# N-CW7_Main.net
KiCad netlist of a schematic drawn in Altium Designer
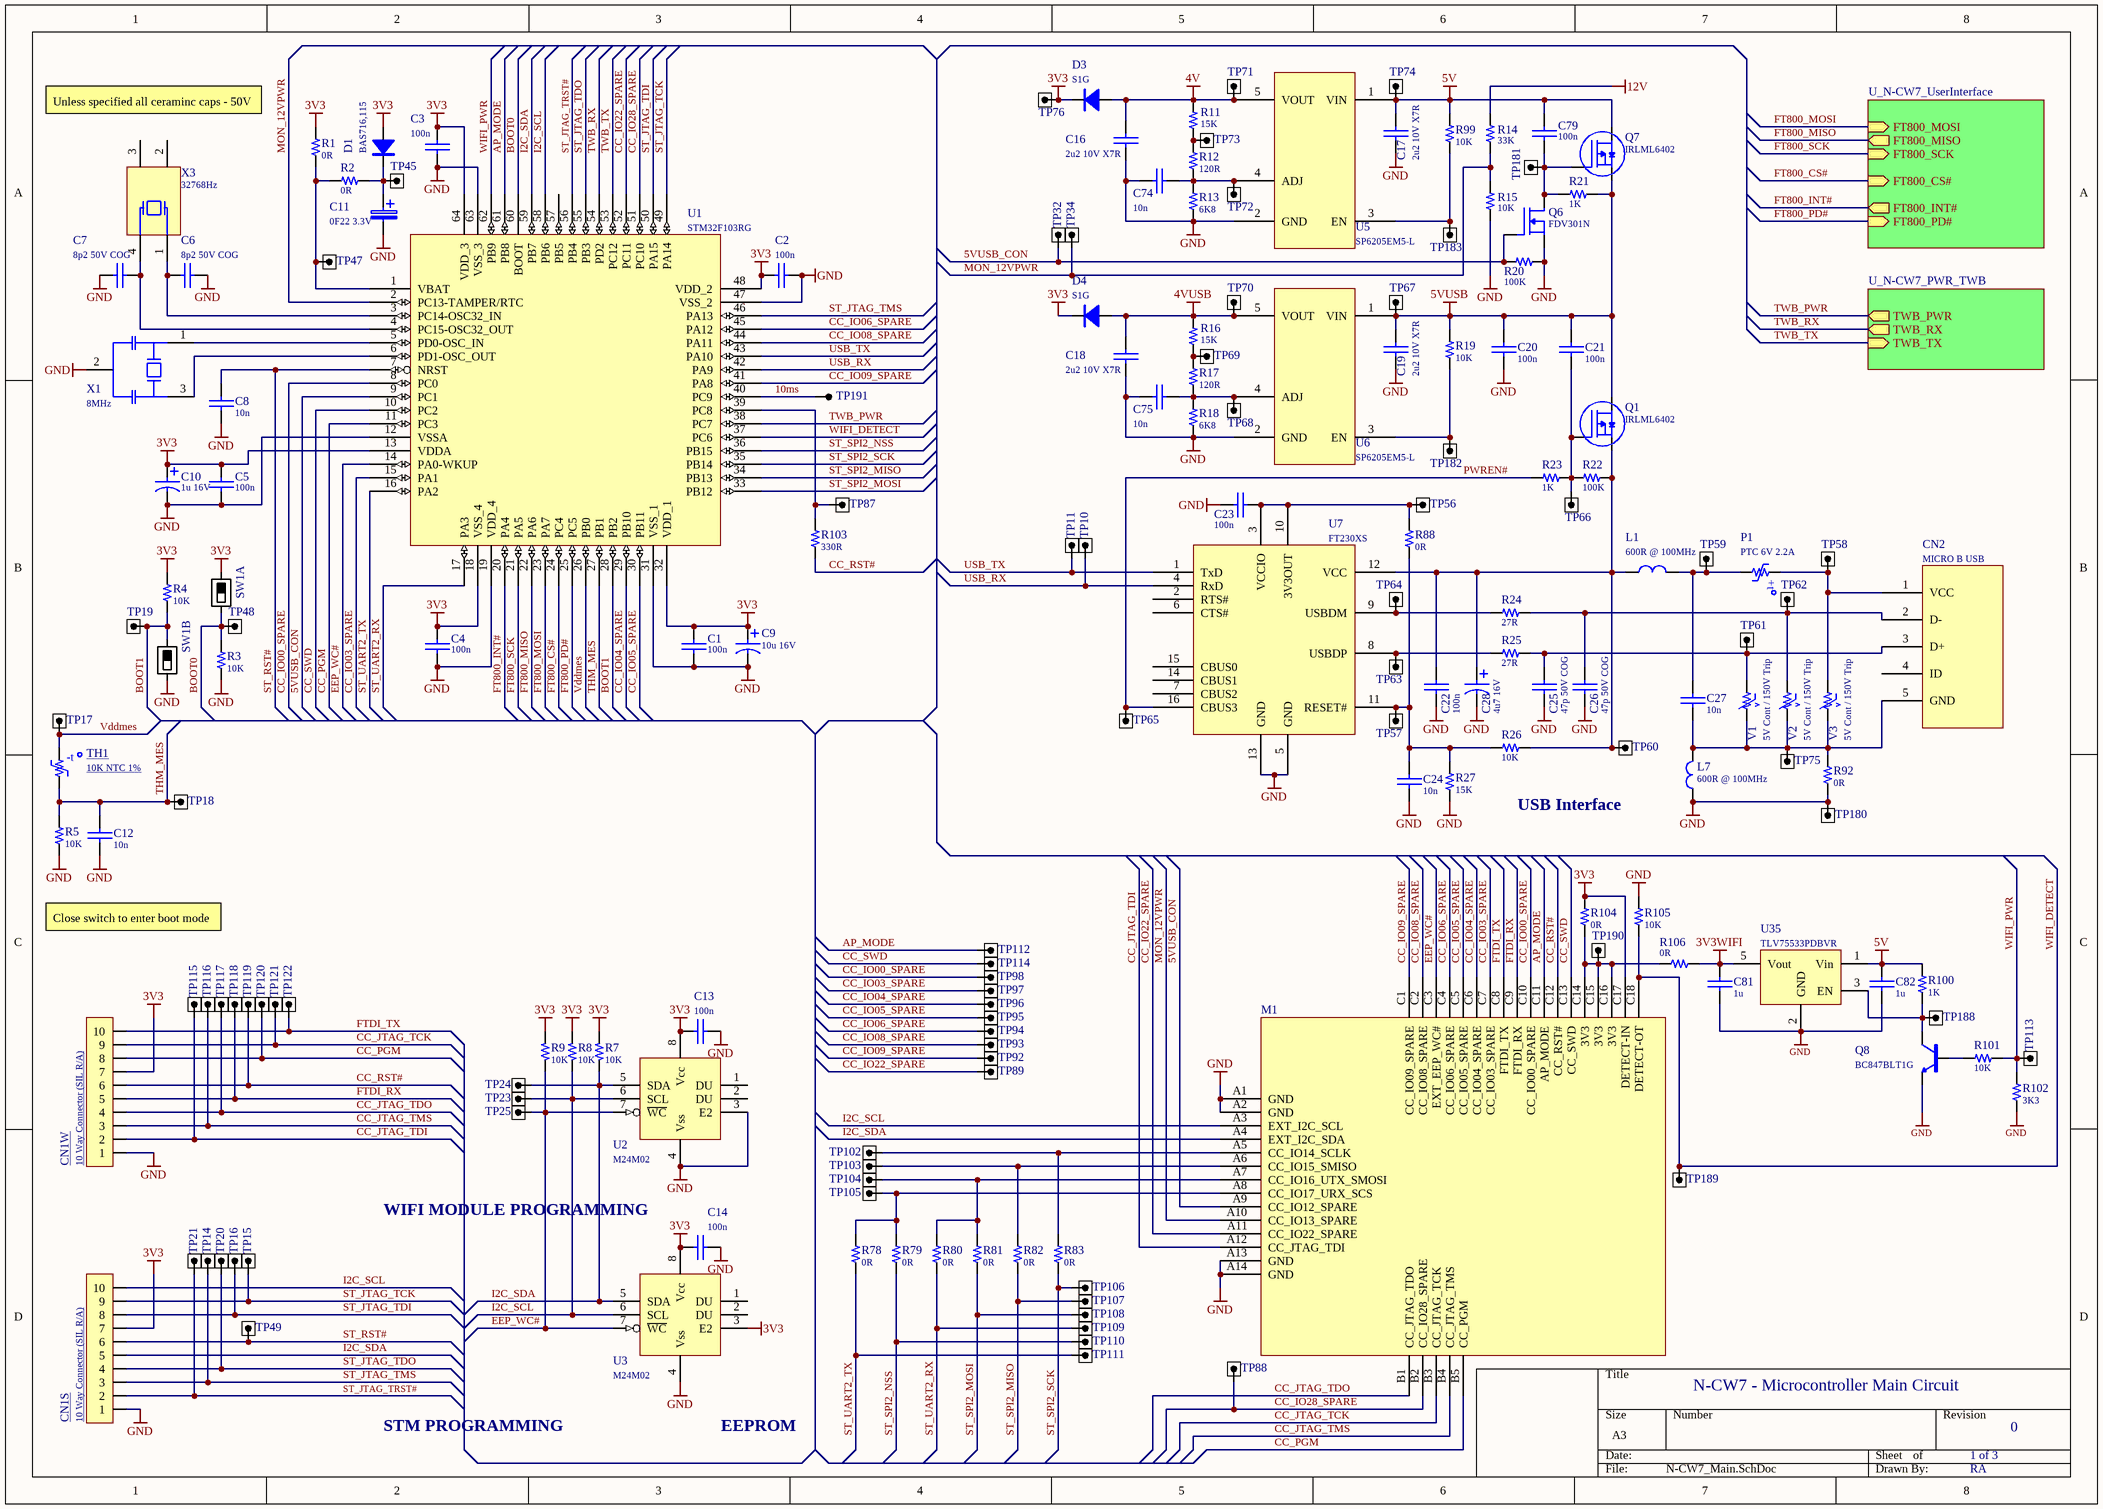
[diagram p0: N-CW7_Main.SchDoc]

(export (version "E")
  (design (tool "Eeschema 10.0.6"))
  (components
    (comp (ref "C1")
      (value "100n")
      (footprint "TDK_0603_T0.80:CAPC1608X08N")
      (description "CAP CER 0.1UF 50V X7R 0603")
      (fields
        (field (name "MANUFACTURER") "TDK")
        (field (name "MANUFACTURER PART NUMBER") "C1608X7R1H104K080AA")
      )
      (libsource (lib "PassiveComponents_Capacitors_Ceramic") (part "TDK_0603_T0.80"))
    )
    (comp (ref "C2")
      (value "100n")
      (footprint "TDK_0603_T0.80:CAPC1608X08N")
      (description "CAP CER 0.1UF 50V X7R 0603")
      (fields
        (field (name "MANUFACTURER") "TDK")
        (field (name "MANUFACTURER PART NUMBER") "C1608X7R1H104K080AA")
      )
      (libsource (lib "PassiveComponents_Capacitors_Ceramic") (part "TDK_0603_T0.80"))
    )
    (comp (ref "C3")
      (value "100n")
      (footprint "TDK_0603_T0.80:CAPC1608X08N")
      (description "CAP CER 0.1UF 50V X7R 0603")
      (fields
        (field (name "MANUFACTURER") "TDK")
        (field (name "MANUFACTURER PART NUMBER") "C1608X7R1H104K080AA")
      )
      (libsource (lib "PassiveComponents_Capacitors_Ceramic") (part "TDK_0603_T0.80"))
    )
    (comp (ref "C4")
      (value "100n")
      (footprint "TDK_0603_T0.80:CAPC1608X08N")
      (description "CAP CER 0.1UF 50V X7R 0603")
      (fields
        (field (name "MANUFACTURER") "TDK")
        (field (name "MANUFACTURER PART NUMBER") "C1608X7R1H104K080AA")
      )
      (libsource (lib "PassiveComponents_Capacitors_Ceramic") (part "TDK_0603_T0.80"))
    )
    (comp (ref "C5")
      (value "100n")
      (footprint "TDK_0603_T0.80:CAPC1608X08N")
      (description "CAP CER 0.1UF 50V X7R 0603")
      (fields
        (field (name "MANUFACTURER") "TDK")
        (field (name "MANUFACTURER PART NUMBER") "C1608X7R1H104K080AA")
      )
      (libsource (lib "PassiveComponents_Capacitors_Ceramic") (part "TDK_0603_T0.80"))
    )
    (comp (ref "C6")
      (value "8p2 50V COG")
      (footprint "KEMET_0603_T0.80:CAPC1608X08N")
      (description "CAP CER 8.2PF 50V C0G/NP0 0603")
      (fields
        (field (name "MANUFACTURER") "KEMET")
        (field (name "MANUFACTURER PART NUMBER") "C0603C829C5GACTU")
      )
      (libsource (lib "PassiveComponents_Capacitors_Ceramic") (part "KEMET_0603_T0.80"))
    )
    (comp (ref "C7")
      (value "8p2 50V COG")
      (footprint "KEMET_0603_T0.80:CAPC1608X08N")
      (description "CAP CER 8.2PF 50V C0G/NP0 0603")
      (fields
        (field (name "MANUFACTURER") "KEMET")
        (field (name "MANUFACTURER PART NUMBER") "C0603C829C5GACTU")
      )
      (libsource (lib "PassiveComponents_Capacitors_Ceramic") (part "KEMET_0603_T0.80"))
    )
    (comp (ref "C8")
      (value "10n")
      (footprint "TDK_0603_T0.80:CAPC1608X08N")
      (description "CAP CER 10000PF 50V X7R 0603")
      (fields
        (field (name "MANUFACTURER") "TDK")
        (field (name "MANUFACTURER PART NUMBER") "C1608X7R1H103K080AA")
      )
      (libsource (lib "PassiveComponents_Capacitors_Ceramic") (part "TDK_0603_T0.80"))
    )
    (comp (ref "C9")
      (value "10u 16V")
      (footprint "KEMET_T494B/3528-21:CAPMP3528X19N")
      (description "CAP TANT 10UF 10% 16V 1411")
      (fields
        (field (name "MANUFACTURER") "KEMET")
        (field (name "MANUFACTURER PART NUMBER") "T494B106K016AT")
      )
      (libsource (lib "PassiveComponents_Capacitors_Tantalum") (part "KEMET_T494B/EIA3528-21"))
    )
    (comp (ref "C10")
      (value "1u 16V")
      (footprint "KEMET_T494A/3216-18:CAPCP3216X16N")
      (description "CAP TANT 1UF 10% 16V 1206")
      (fields
        (field (name "MANUFACTURER") "KEMET")
        (field (name "MANUFACTURER PART NUMBER") "T494A105K016AT")
      )
      (libsource (lib "PassiveComponents_Capacitors_Tantalum") (part "KEMET_T494A/EIA3216-18"))
    )
    (comp (ref "C11")
      (value "0F22 3.3V")
      (footprint "ELNA_RSCSK2243R3D02008U")
      (description "CAP 220MF -20% +80% 3.3V SMD")
      (fields
        (field (name "MANUFACTURER") "Elna")
        (field (name "MANUFACTURER PART NUMBER") "RSCSK2243R3D02008U")
      )
      (libsource (lib "PassiveComponents_Capacitors_Electrolytic") (part "ELNA_RSCSK2243R3D02008U"))
    )
    (comp (ref "C12")
      (value "10n")
      (footprint "TDK_0603_T0.80:CAPC1608X08N")
      (description "CAP CER 10000PF 50V X7R 0603")
      (fields
        (field (name "MANUFACTURER") "TDK")
        (field (name "MANUFACTURER PART NUMBER") "C1608X7R1H103K080AA")
      )
      (libsource (lib "PassiveComponents_Capacitors_Ceramic") (part "TDK_0603_T0.80"))
    )
    (comp (ref "C13")
      (value "100n")
      (footprint "TDK_0603_T0.80:CAPC1608X08N")
      (description "CAP CER 0.1UF 50V X7R 0603")
      (fields
        (field (name "MANUFACTURER") "TDK")
        (field (name "MANUFACTURER PART NUMBER") "C1608X7R1H104K080AA")
      )
      (libsource (lib "PassiveComponents_Capacitors_Ceramic") (part "TDK_0603_T0.80"))
    )
    (comp (ref "C14")
      (value "100n")
      (footprint "TDK_0603_T0.80:CAPC1608X08N")
      (description "CAP CER 0.1UF 50V X7R 0603")
      (fields
        (field (name "MANUFACTURER") "TDK")
        (field (name "MANUFACTURER PART NUMBER") "C1608X7R1H104K080AA")
      )
      (libsource (lib "PassiveComponents_Capacitors_Ceramic") (part "TDK_0603_T0.80"))
    )
    (comp (ref "C16")
      (value "2u2 10V X7R")
      (footprint "TDK_0603_T0.80:CAPC1608X08N")
      (description "CAP CER 2.2UF 10V X7R 0603")
      (fields
        (field (name "MANUFACTURER") "TDK")
        (field (name "MANUFACTURER PART NUMBER") "C1608X7R1A225K080AC")
      )
      (libsource (lib "PassiveComponents_Capacitors_Ceramic") (part "TDK_0603_T0.80"))
    )
    (comp (ref "C17")
      (value "2u2 10V X7R")
      (footprint "TDK_0603_T0.80:CAPC1608X08N")
      (description "CAP CER 2.2UF 10V X7R 0603")
      (fields
        (field (name "MANUFACTURER") "TDK")
        (field (name "MANUFACTURER PART NUMBER") "C1608X7R1A225K080AC")
      )
      (libsource (lib "PassiveComponents_Capacitors_Ceramic") (part "TDK_0603_T0.80"))
    )
    (comp (ref "C18")
      (value "2u2 10V X7R")
      (footprint "TDK_0603_T0.80:CAPC1608X08N")
      (description "CAP CER 2.2UF 10V X7R 0603")
      (fields
        (field (name "MANUFACTURER") "TDK")
        (field (name "MANUFACTURER PART NUMBER") "C1608X7R1A225K080AC")
      )
      (libsource (lib "PassiveComponents_Capacitors_Ceramic") (part "TDK_0603_T0.80"))
    )
    (comp (ref "C19")
      (value "2u2 10V X7R")
      (footprint "TDK_0603_T0.80:CAPC1608X08N")
      (description "CAP CER 2.2UF 10V X7R 0603")
      (fields
        (field (name "MANUFACTURER") "TDK")
        (field (name "MANUFACTURER PART NUMBER") "C1608X7R1A225K080AC")
      )
      (libsource (lib "PassiveComponents_Capacitors_Ceramic") (part "TDK_0603_T0.80"))
    )
    (comp (ref "C20")
      (value "100n")
      (footprint "TDK_0603_T0.80:CAPC1608X08N")
      (description "CAP CER 0.1UF 50V X7R 0603")
      (fields
        (field (name "MANUFACTURER") "TDK")
        (field (name "MANUFACTURER PART NUMBER") "C1608X7R1H104K080AA")
      )
      (libsource (lib "PassiveComponents_Capacitors_Ceramic") (part "TDK_0603_T0.80"))
    )
    (comp (ref "C21")
      (value "100n")
      (footprint "TDK_0603_T0.80:CAPC1608X08N")
      (description "CAP CER 0.1UF 50V X7R 0603")
      (fields
        (field (name "MANUFACTURER") "TDK")
        (field (name "MANUFACTURER PART NUMBER") "C1608X7R1H104K080AA")
      )
      (libsource (lib "PassiveComponents_Capacitors_Ceramic") (part "TDK_0603_T0.80"))
    )
    (comp (ref "C22")
      (value "100n")
      (footprint "TDK_0603_T0.80:CAPC1608X08N")
      (description "CAP CER 0.1UF 50V X7R 0603")
      (fields
        (field (name "MANUFACTURER") "TDK")
        (field (name "MANUFACTURER PART NUMBER") "C1608X7R1H104K080AA")
      )
      (libsource (lib "PassiveComponents_Capacitors_Ceramic") (part "TDK_0603_T0.80"))
    )
    (comp (ref "C23")
      (value "100n")
      (footprint "TDK_0603_T0.80:CAPC1608X08N")
      (description "CAP CER 0.1UF 50V X7R 0603")
      (fields
        (field (name "MANUFACTURER") "TDK")
        (field (name "MANUFACTURER PART NUMBER") "C1608X7R1H104K080AA")
      )
      (libsource (lib "PassiveComponents_Capacitors_Ceramic") (part "TDK_0603_T0.80"))
    )
    (comp (ref "C24")
      (value "10n")
      (footprint "TDK_0603_T0.80:CAPC1608X08N")
      (description "CAP CER 10000PF 50V X7R 0603")
      (fields
        (field (name "MANUFACTURER") "TDK")
        (field (name "MANUFACTURER PART NUMBER") "C1608X7R1H103K080AA")
      )
      (libsource (lib "PassiveComponents_Capacitors_Ceramic") (part "TDK_0603_T0.80"))
    )
    (comp (ref "C25")
      (value "47p 50V COG")
      (footprint "TDK_0603_T0.80:CAPC1608X08N")
      (description "CAP CER 47PF 50V C0G 0603")
      (fields
        (field (name "MANUFACTURER") "TDK")
        (field (name "MANUFACTURER PART NUMBER") "C1608C0G1H470J080AA")
      )
      (libsource (lib "PassiveComponents_Capacitors_Ceramic") (part "TDK_0603_T0.80"))
    )
    (comp (ref "C26")
      (value "47p 50V COG")
      (footprint "TDK_0603_T0.80:CAPC1608X08N")
      (description "CAP CER 47PF 50V C0G 0603")
      (fields
        (field (name "MANUFACTURER") "TDK")
        (field (name "MANUFACTURER PART NUMBER") "C1608C0G1H470J080AA")
      )
      (libsource (lib "PassiveComponents_Capacitors_Ceramic") (part "TDK_0603_T0.80"))
    )
    (comp (ref "C27")
      (value "10n")
      (footprint "TDK_0603_T0.80:CAPC1608X08N")
      (description "CAP CER 10000PF 50V X7R 0603")
      (fields
        (field (name "MANUFACTURER") "TDK")
        (field (name "MANUFACTURER PART NUMBER") "C1608X7R1H103K080AA")
      )
      (libsource (lib "PassiveComponents_Capacitors_Ceramic") (part "TDK_0603_T0.80"))
    )
    (comp (ref "C28")
      (value "4u7 16V")
      (footprint "KEMET_T494A/3216-18:CAPCP3216X16N")
      (description "CAP TANT 4.7UF 10% 16V 1206")
      (fields
        (field (name "MANUFACTURER") "KEMET")
        (field (name "MANUFACTURER PART NUMBER") "T494A475K016AT")
      )
      (libsource (lib "PassiveComponents_Capacitors_Tantalum") (part "KEMET_T494A/EIA3216-18"))
    )
    (comp (ref "C74")
      (value "10n")
      (footprint "TDK_0603_T0.80:CAPC1608X08N")
      (description "CAP CER 10000PF 50V X7R 0603")
      (fields
        (field (name "MANUFACTURER") "TDK")
        (field (name "MANUFACTURER PART NUMBER") "C1608X7R1H103K080AA")
      )
      (libsource (lib "PassiveComponents_Capacitors_Ceramic") (part "TDK_0603_T0.80"))
    )
    (comp (ref "C75")
      (value "10n")
      (footprint "TDK_0603_T0.80:CAPC1608X08N")
      (description "CAP CER 10000PF 50V X7R 0603")
      (fields
        (field (name "MANUFACTURER") "TDK")
        (field (name "MANUFACTURER PART NUMBER") "C1608X7R1H103K080AA")
      )
      (libsource (lib "PassiveComponents_Capacitors_Ceramic") (part "TDK_0603_T0.80"))
    )
    (comp (ref "C79")
      (value "100n")
      (footprint "TDK_0603_T0.80:CAPC1608X08N")
      (description "CAP CER 0.1UF 50V X7R 0603")
      (fields
        (field (name "MANUFACTURER") "TDK")
        (field (name "MANUFACTURER PART NUMBER") "C1608X7R1H104K080AA")
      )
      (libsource (lib "PassiveComponents_Capacitors_Ceramic") (part "TDK_0603_T0.80"))
    )
    (comp (ref "C81")
      (value "1u")
      (footprint "KEMET_1210_T1.55:CAPC3225X16N")
      (description "CAP CER 1UF 50V X5R 1210")
      (fields
        (field (name "MANUFACTURER") "KEMET")
        (field (name "MANUFACTURER PART NUMBER") "C1210C105K5PACTU")
      )
      (libsource (lib "PassiveComponents_Capacitors_Ceramic") (part "KEMET_1210_T1.55"))
    )
    (comp (ref "C82")
      (value "1u")
      (footprint "KEMET_1210_T1.55:CAPC3225X16N")
      (description "CAP CER 1UF 50V X5R 1210")
      (fields
        (field (name "MANUFACTURER") "KEMET")
        (field (name "MANUFACTURER PART NUMBER") "C1210C105K5PACTU")
      )
      (libsource (lib "PassiveComponents_Capacitors_Ceramic") (part "KEMET_1210_T1.55"))
    )
    (comp (ref "CN1S")
      (value "10 Way Connector (SIL R/A)")
      (footprint "SULLINS_PPTC101LGBN-RC")
      (description "CONN HDR 10POS 0.1 TIN PCB R/A")
      (fields
        (field (name "MANUFACTURER") "Sullins")
        (field (name "MANUFACTURER PART NUMBER") "PPTC101LGBN-RC")
      )
      (libsource (lib "Connectors") (part "SULLINS_10W_SIL_HDR_RA_2.54MM"))
    )
    (comp (ref "CN1W")
      (value "10 Way Connector (SIL R/A)")
      (footprint "SULLINS_PPTC101LGBN-RC")
      (description "CONN HDR 10POS 0.1 TIN PCB R/A")
      (fields
        (field (name "MANUFACTURER") "Sullins")
        (field (name "MANUFACTURER PART NUMBER") "PPTC101LGBN-RC")
      )
      (libsource (lib "Connectors") (part "SULLINS_10W_SIL_HDR_RA_2.54MM"))
    )
    (comp (ref "CN2")
      (value "MICRO B USB")
      (footprint "MOLEX:47346-1001")
      (description "CONN RCPT USB2.0 MICRO B SMD R/A")
      (fields (field (name "MANUFACTURER") "Molex") (field (name "MANUFACTURER PART NUMBER") "47346-1001"))
      (libsource (lib "Connectors") (part "MOLEX_USB_MICRO_B_SMD_RA"))
    )
    (comp (ref "D1")
      (value "BAS716,115")
      (footprint "NEXPERIA_BAS716,115_SOD523:SODFL160X65-2N")
      (description "DIODE STANDARD 75V 200MA SOD523")
      (fields (field (name "MANUFACTURER") "Nexperia") (field (name "MANUFACTURER PART NUMBER") "BAS716115"))
      (libsource (lib "DiscreteSemiconductors_Diodes_Rectifier") (part "NEXPERIA_BAS716,115_SOD523"))
    )
    (comp (ref "D3")
      (value "S1G")
      (footprint "DIODESINC_S1G_SMA_D0214AC:DIOM4326X24N")
      (description "DIODE GEN PURP 400V 1A SMA")
      (fields (field (name "MANUFACTURER") "Diodes") (field (name "MANUFACTURER PART NUMBER") "S1G-13-F"))
      (libsource (lib "DiscreteSemiconductors_Diodes_Rectifier") (part "DIODESINC_S1G_SMA_D0214AC"))
    )
    (comp (ref "D4")
      (value "S1G")
      (footprint "DIODESINC_S1G_SMA_D0214AC:DIOM4326X24N")
      (description "DIODE GEN PURP 400V 1A SMA")
      (fields (field (name "MANUFACTURER") "Diodes") (field (name "MANUFACTURER PART NUMBER") "S1G-13-F"))
      (libsource (lib "DiscreteSemiconductors_Diodes_Rectifier") (part "DIODESINC_S1G_SMA_D0214AC"))
    )
    (comp (ref "L1")
      (value "600R @ 100MHz")
      (footprint "LAIRD_MI0805K601R-10:INDC2012X09N")
      (description "FERRITE BEAD 600 OHM 0805 1LN")
      (fields
        (field (name "MANUFACTURER") "Laird")
        (field (name "MANUFACTURER PART NUMBER") "MI0805K601R-10")
      )
      (libsource (lib "PassiveComponents_Inductors") (part "LAIRD_MI0805K601R-10"))
    )
    (comp (ref "L7")
      (value "600R @ 100MHz")
      (footprint "LAIRD_MI0805K601R-10:INDC2012X09N")
      (description "FERRITE BEAD 600 OHM 0805 1LN")
      (fields
        (field (name "MANUFACTURER") "Laird")
        (field (name "MANUFACTURER PART NUMBER") "MI0805K601R-10")
      )
      (libsource (lib "PassiveComponents_Inductors") (part "LAIRD_MI0805K601R-10"))
    )
    (comp (ref "M1")
      (value "MB-WIFI-CC3200Rev00")
      (footprint "MB-WIFI-CC3200Rev00")
      (description "Module - Wi-Fi Module (CC3200)")
      (libsource (lib "CustomModules") (part "MB-WIFI-CC3200Rev00"))
    )
    (comp (ref "P1")
      (value "PTC 6V 2.2A")
      (footprint "BOURNS_MF-MSMF110-2:INDC4632X08N")
      (description "PTC RESET FUSE 24V 1.1A 1812")
      (fields
        (field (name "MANUFACTURER") "Bourns")
        (field (name "MANUFACTURER PART NUMBER") "MF-MSMF110/24X-2")
      )
      (libsource (lib "CircuitProtection_Fuses") (part "BOURNS_MF-MSMF110-2"))
    )
    (comp (ref "Q1")
      (value "IRLML6402")
      (footprint "IR_IRLML6402TRPBF_SOT23:SOT95P237X112-3N")
      (description "MOSFET P-CH 20V 3.7A SOT23")
      (fields
        (field (name "MANUFACTURER") "Infineon")
        (field (name "MANUFACTURER PART NUMBER") "IRLML6402TRPBF")
      )
      (libsource (lib "DiscreteSemiconductors_Transistors_JFETs") (part "IR_IRLML6402TRPBF_SOT23"))
    )
    (comp (ref "Q6")
      (value "FDV301N")
      (footprint "ONSEMI_FDV301N_SOT23:SOT95P230X110-3N")
      (description "MOSFET N-CH 25V 220MA SOT23")
      (fields (field (name "MANUFACTURER") "ON Semiconductor / Fairchild"))
      (libsource (lib "DiscreteSemiconductors_Transistors_JFETs") (part "ONSEMI_FDV301N_SOT23"))
    )
    (comp (ref "Q7")
      (value "IRLML6402")
      (footprint "IR_IRLML6402TRPBF_SOT23:SOT95P237X112-3N")
      (description "MOSFET P-CH 20V 3.7A SOT23")
      (fields
        (field (name "MANUFACTURER") "Infineon")
        (field (name "MANUFACTURER PART NUMBER") "IRLML6402TRPBF")
      )
      (libsource (lib "DiscreteSemiconductors_Transistors_JFETs") (part "IR_IRLML6402TRPBF_SOT23"))
    )
    (comp (ref "Q8")
      (value "BC847BLT1G")
      (footprint "ONSEMI_BC847BLT1G_SOT23:SOT95P230X110-3N")
      (description "TRANS NPN 45V 100MA SOT23-3")
      (fields (field (name "MANUFACTURER") "ON Semiconductor"))
      (libsource (lib "DiscreteSemiconductors_Transistors_BJTs") (part "ONSEMI_BC847BLT1G_SOT23"))
    )
    (comp (ref "R1")
      (value "0R")
      (footprint "YAGEO_0603_T0.55:RESC1608X06N")
      (description "RES 0 OHM JUMPER 1/10W 0603")
      (fields
        (field (name "MANUFACTURER") "Yageo")
        (field (name "MANUFACTURER PART NUMBER") "RC0603FR-070RL")
      )
      (libsource (lib "PassiveComponents_Resistors_ChipSMD") (part "YAGEO_0603_T0.55"))
    )
    (comp (ref "R2")
      (value "0R")
      (footprint "YAGEO_0603_T0.55:RESC1608X06N")
      (description "RES 0 OHM JUMPER 1/10W 0603")
      (fields
        (field (name "MANUFACTURER") "Yageo")
        (field (name "MANUFACTURER PART NUMBER") "RC0603FR-070RL")
      )
      (libsource (lib "PassiveComponents_Resistors_ChipSMD") (part "YAGEO_0603_T0.55"))
    )
    (comp (ref "R3")
      (value "10K")
      (footprint "YAGEO_0603_T0.55:RESC1608X06N")
      (description "RES 10K OHM 1% 1/10W 0603")
      (fields
        (field (name "MANUFACTURER") "Yageo")
        (field (name "MANUFACTURER PART NUMBER") "RC0603FR-0710KL")
      )
      (libsource (lib "PassiveComponents_Resistors_ChipSMD") (part "YAGEO_0603_T0.55"))
    )
    (comp (ref "R4")
      (value "10K")
      (footprint "YAGEO_0603_T0.55:RESC1608X06N")
      (description "RES 10K OHM 1% 1/10W 0603")
      (fields
        (field (name "MANUFACTURER") "Yageo")
        (field (name "MANUFACTURER PART NUMBER") "RC0603FR-0710KL")
      )
      (libsource (lib "PassiveComponents_Resistors_ChipSMD") (part "YAGEO_0603_T0.55"))
    )
    (comp (ref "R5")
      (value "10K")
      (footprint "YAGEO_0603_T0.55:RESC1608X06N")
      (description "RES 10K OHM 1% 1/10W 0603")
      (fields
        (field (name "MANUFACTURER") "Yageo")
        (field (name "MANUFACTURER PART NUMBER") "RC0603FR-0710KL")
      )
      (libsource (lib "PassiveComponents_Resistors_ChipSMD") (part "YAGEO_0603_T0.55"))
    )
    (comp (ref "R7")
      (value "10K")
      (footprint "YAGEO_0603_T0.55:RESC1608X06N")
      (description "RES 10K OHM 1% 1/10W 0603")
      (fields
        (field (name "MANUFACTURER") "Yageo")
        (field (name "MANUFACTURER PART NUMBER") "RC0603FR-0710KL")
      )
      (libsource (lib "PassiveComponents_Resistors_ChipSMD") (part "YAGEO_0603_T0.55"))
    )
    (comp (ref "R8")
      (value "10K")
      (footprint "YAGEO_0603_T0.55:RESC1608X06N")
      (description "RES 10K OHM 1% 1/10W 0603")
      (fields
        (field (name "MANUFACTURER") "Yageo")
        (field (name "MANUFACTURER PART NUMBER") "RC0603FR-0710KL")
      )
      (libsource (lib "PassiveComponents_Resistors_ChipSMD") (part "YAGEO_0603_T0.55"))
    )
    (comp (ref "R9")
      (value "10K")
      (footprint "YAGEO_0603_T0.55:RESC1608X06N")
      (description "RES 10K OHM 1% 1/10W 0603")
      (fields
        (field (name "MANUFACTURER") "Yageo")
        (field (name "MANUFACTURER PART NUMBER") "RC0603FR-0710KL")
      )
      (libsource (lib "PassiveComponents_Resistors_ChipSMD") (part "YAGEO_0603_T0.55"))
    )
    (comp (ref "R11")
      (value "15K")
      (footprint "YAGEO_0603_T0.55:RESC1608X06N")
      (description "RES 15K OHM 1% 1/10W 0603")
      (fields
        (field (name "MANUFACTURER") "Yageo")
        (field (name "MANUFACTURER PART NUMBER") "RC0603FR-0715KL")
      )
      (libsource (lib "PassiveComponents_Resistors_ChipSMD") (part "YAGEO_0603_T0.55"))
    )
    (comp (ref "R12")
      (value "120R")
      (footprint "YAGEO_0603_T0.55:RESC1608X06N")
      (description "RES 120 OHM 1% 1/10W 0603")
      (fields
        (field (name "MANUFACTURER") "Yageo")
        (field (name "MANUFACTURER PART NUMBER") "RC0603FR-07120RL")
      )
      (libsource (lib "PassiveComponents_Resistors_ChipSMD") (part "YAGEO_0603_T0.55"))
    )
    (comp (ref "R13")
      (value "6K8")
      (footprint "YAGEO_0603_T0.55:RESC1608X06N")
      (description "RES 6.8K OHM 1% 1/10W 0603")
      (fields
        (field (name "MANUFACTURER") "Yageo")
        (field (name "MANUFACTURER PART NUMBER") "RC0603FR-076K8L")
      )
      (libsource (lib "PassiveComponents_Resistors_ChipSMD") (part "YAGEO_0603_T0.55"))
    )
    (comp (ref "R14")
      (value "33K")
      (footprint "YAGEO_0603_T0.55:RESC1608X06N")
      (description "RES 33K OHM 1% 1/10W 0603")
      (fields
        (field (name "MANUFACTURER") "Yageo")
        (field (name "MANUFACTURER PART NUMBER") "RC0603FR-0733KL")
      )
      (libsource (lib "PassiveComponents_Resistors_ChipSMD") (part "YAGEO_0603_T0.55"))
    )
    (comp (ref "R15")
      (value "10K")
      (footprint "YAGEO_0603_T0.55:RESC1608X06N")
      (description "RES 10K OHM 1% 1/10W 0603")
      (fields
        (field (name "MANUFACTURER") "Yageo")
        (field (name "MANUFACTURER PART NUMBER") "RC0603FR-0710KL")
      )
      (libsource (lib "PassiveComponents_Resistors_ChipSMD") (part "YAGEO_0603_T0.55"))
    )
    (comp (ref "R16")
      (value "15K")
      (footprint "YAGEO_0603_T0.55:RESC1608X06N")
      (description "RES 15K OHM 1% 1/10W 0603")
      (fields
        (field (name "MANUFACTURER") "Yageo")
        (field (name "MANUFACTURER PART NUMBER") "RC0603FR-0715KL")
      )
      (libsource (lib "PassiveComponents_Resistors_ChipSMD") (part "YAGEO_0603_T0.55"))
    )
    (comp (ref "R17")
      (value "120R")
      (footprint "YAGEO_0603_T0.55:RESC1608X06N")
      (description "RES 120 OHM 1% 1/10W 0603")
      (fields
        (field (name "MANUFACTURER") "Yageo")
        (field (name "MANUFACTURER PART NUMBER") "RC0603FR-07120RL")
      )
      (libsource (lib "PassiveComponents_Resistors_ChipSMD") (part "YAGEO_0603_T0.55"))
    )
    (comp (ref "R18")
      (value "6K8")
      (footprint "YAGEO_0603_T0.55:RESC1608X06N")
      (description "RES 6.8K OHM 1% 1/10W 0603")
      (fields
        (field (name "MANUFACTURER") "Yageo")
        (field (name "MANUFACTURER PART NUMBER") "RC0603FR-076K8L")
      )
      (libsource (lib "PassiveComponents_Resistors_ChipSMD") (part "YAGEO_0603_T0.55"))
    )
    (comp (ref "R19")
      (value "10K")
      (footprint "YAGEO_0603_T0.55:RESC1608X06N")
      (description "RES 10K OHM 1% 1/10W 0603")
      (fields
        (field (name "MANUFACTURER") "Yageo")
        (field (name "MANUFACTURER PART NUMBER") "RC0603FR-0710KL")
      )
      (libsource (lib "PassiveComponents_Resistors_ChipSMD") (part "YAGEO_0603_T0.55"))
    )
    (comp (ref "R20")
      (value "100K")
      (footprint "YAGEO_0603_T0.55:RESC1608X06N")
      (description "RES 100K OHM 1% 1/10W 0603")
      (fields
        (field (name "MANUFACTURER") "Yageo")
        (field (name "MANUFACTURER PART NUMBER") "RC0603FR-07100KL")
      )
      (libsource (lib "PassiveComponents_Resistors_ChipSMD") (part "YAGEO_0603_T0.55"))
    )
    (comp (ref "R21")
      (value "1K")
      (footprint "YAGEO_0603_T0.55:RESC1608X06N")
      (description "RES 1K OHM 1% 1/10W 0603")
      (fields
        (field (name "MANUFACTURER") "Yageo")
        (field (name "MANUFACTURER PART NUMBER") "RC0603FR-071KL")
      )
      (libsource (lib "PassiveComponents_Resistors_ChipSMD") (part "YAGEO_0603_T0.55"))
    )
    (comp (ref "R22")
      (value "100K")
      (footprint "YAGEO_0603_T0.55:RESC1608X06N")
      (description "RES 100K OHM 1% 1/10W 0603")
      (fields
        (field (name "MANUFACTURER") "Yageo")
        (field (name "MANUFACTURER PART NUMBER") "RC0603FR-07100KL")
      )
      (libsource (lib "PassiveComponents_Resistors_ChipSMD") (part "YAGEO_0603_T0.55"))
    )
    (comp (ref "R23")
      (value "1K")
      (footprint "YAGEO_0603_T0.55:RESC1608X06N")
      (description "RES 1K OHM 1% 1/10W 0603")
      (fields
        (field (name "MANUFACTURER") "Yageo")
        (field (name "MANUFACTURER PART NUMBER") "RC0603FR-071KL")
      )
      (libsource (lib "PassiveComponents_Resistors_ChipSMD") (part "YAGEO_0603_T0.55"))
    )
    (comp (ref "R24")
      (value "27R")
      (footprint "YAGEO_0603_T0.55:RESC1608X06N")
      (description "RES 27 OHM 1% 1/10W 0603")
      (fields
        (field (name "MANUFACTURER") "Yageo")
        (field (name "MANUFACTURER PART NUMBER") "RC0603FR-0727RL")
      )
      (libsource (lib "PassiveComponents_Resistors_ChipSMD") (part "YAGEO_0603_T0.55"))
    )
    (comp (ref "R25")
      (value "27R")
      (footprint "YAGEO_0603_T0.55:RESC1608X06N")
      (description "RES 27 OHM 1% 1/10W 0603")
      (fields
        (field (name "MANUFACTURER") "Yageo")
        (field (name "MANUFACTURER PART NUMBER") "RC0603FR-0727RL")
      )
      (libsource (lib "PassiveComponents_Resistors_ChipSMD") (part "YAGEO_0603_T0.55"))
    )
    (comp (ref "R26")
      (value "10K")
      (footprint "YAGEO_0603_T0.55:RESC1608X06N")
      (description "RES 10K OHM 1% 1/10W 0603")
      (fields
        (field (name "MANUFACTURER") "Yageo")
        (field (name "MANUFACTURER PART NUMBER") "RC0603FR-0710KL")
      )
      (libsource (lib "PassiveComponents_Resistors_ChipSMD") (part "YAGEO_0603_T0.55"))
    )
    (comp (ref "R27")
      (value "15K")
      (footprint "YAGEO_0603_T0.55:RESC1608X06N")
      (description "RES 15K OHM 1% 1/10W 0603")
      (fields
        (field (name "MANUFACTURER") "Yageo")
        (field (name "MANUFACTURER PART NUMBER") "RC0603FR-0715KL")
      )
      (libsource (lib "PassiveComponents_Resistors_ChipSMD") (part "YAGEO_0603_T0.55"))
    )
    (comp (ref "R78")
      (value "0R")
      (footprint "YAGEO_0603_T0.55:RESC1608X06N")
      (description "RES 0 OHM JUMPER 1/10W 0603")
      (fields
        (field (name "MANUFACTURER") "Yageo")
        (field (name "MANUFACTURER PART NUMBER") "RC0603FR-070RL")
      )
      (libsource (lib "PassiveComponents_Resistors_ChipSMD") (part "YAGEO_0603_T0.55"))
    )
    (comp (ref "R79")
      (value "0R")
      (footprint "YAGEO_0603_T0.55:RESC1608X06N")
      (description "RES 0 OHM JUMPER 1/10W 0603")
      (fields
        (field (name "MANUFACTURER") "Yageo")
        (field (name "MANUFACTURER PART NUMBER") "RC0603FR-070RL")
      )
      (libsource (lib "PassiveComponents_Resistors_ChipSMD") (part "YAGEO_0603_T0.55"))
    )
    (comp (ref "R80")
      (value "0R")
      (footprint "YAGEO_0603_T0.55:RESC1608X06N")
      (description "RES 0 OHM JUMPER 1/10W 0603")
      (fields
        (field (name "MANUFACTURER") "Yageo")
        (field (name "MANUFACTURER PART NUMBER") "RC0603FR-070RL")
      )
      (libsource (lib "PassiveComponents_Resistors_ChipSMD") (part "YAGEO_0603_T0.55"))
    )
    (comp (ref "R81")
      (value "0R")
      (footprint "YAGEO_0603_T0.55:RESC1608X06N")
      (description "RES 0 OHM JUMPER 1/10W 0603")
      (fields
        (field (name "MANUFACTURER") "Yageo")
        (field (name "MANUFACTURER PART NUMBER") "RC0603FR-070RL")
      )
      (libsource (lib "PassiveComponents_Resistors_ChipSMD") (part "YAGEO_0603_T0.55"))
    )
    (comp (ref "R82")
      (value "0R")
      (footprint "YAGEO_0603_T0.55:RESC1608X06N")
      (description "RES 0 OHM JUMPER 1/10W 0603")
      (fields
        (field (name "MANUFACTURER") "Yageo")
        (field (name "MANUFACTURER PART NUMBER") "RC0603FR-070RL")
      )
      (libsource (lib "PassiveComponents_Resistors_ChipSMD") (part "YAGEO_0603_T0.55"))
    )
    (comp (ref "R83")
      (value "0R")
      (footprint "YAGEO_0603_T0.55:RESC1608X06N")
      (description "RES 0 OHM JUMPER 1/10W 0603")
      (fields
        (field (name "MANUFACTURER") "Yageo")
        (field (name "MANUFACTURER PART NUMBER") "RC0603FR-070RL")
      )
      (libsource (lib "PassiveComponents_Resistors_ChipSMD") (part "YAGEO_0603_T0.55"))
    )
    (comp (ref "R88")
      (value "0R")
      (footprint "YAGEO_0603_T0.55:RESC1608X06N")
      (description "RES 0 OHM JUMPER 1/10W 0603")
      (fields
        (field (name "MANUFACTURER") "Yageo")
        (field (name "MANUFACTURER PART NUMBER") "RC0603FR-070RL")
      )
      (libsource (lib "PassiveComponents_Resistors_ChipSMD") (part "YAGEO_0603_T0.55"))
    )
    (comp (ref "R92")
      (value "0R")
      (footprint "YAGEO_0603_T0.55:RESC1608X06N")
      (description "RES 0 OHM JUMPER 1/10W 0603")
      (fields
        (field (name "MANUFACTURER") "Yageo")
        (field (name "MANUFACTURER PART NUMBER") "RC0603FR-070RL")
      )
      (libsource (lib "PassiveComponents_Resistors_ChipSMD") (part "YAGEO_0603_T0.55"))
    )
    (comp (ref "R99")
      (value "10K")
      (footprint "YAGEO_0603_T0.55:RESC1608X06N")
      (description "RES 10K OHM 1% 1/10W 0603")
      (fields
        (field (name "MANUFACTURER") "Yageo")
        (field (name "MANUFACTURER PART NUMBER") "RC0603FR-0710KL")
      )
      (libsource (lib "PassiveComponents_Resistors_ChipSMD") (part "YAGEO_0603_T0.55"))
    )
    (comp (ref "R100")
      (value "1K")
      (footprint "YAGEO_0603_T0.55:RESC1608X06N")
      (description "RES 1K OHM 1% 1/10W 0603")
      (fields
        (field (name "MANUFACTURER") "Yageo")
        (field (name "MANUFACTURER PART NUMBER") "RC0603FR-071KL")
      )
      (libsource (lib "PassiveComponents_Resistors_ChipSMD") (part "YAGEO_0603_T0.55"))
    )
    (comp (ref "R101")
      (value "10K")
      (footprint "YAGEO_0603_T0.55:RESC1608X06N")
      (description "RES 10K OHM 1% 1/10W 0603")
      (fields
        (field (name "MANUFACTURER") "Yageo")
        (field (name "MANUFACTURER PART NUMBER") "RC0603FR-0710KL")
      )
      (libsource (lib "PassiveComponents_Resistors_ChipSMD") (part "YAGEO_0603_T0.55"))
    )
    (comp (ref "R102")
      (value "3K3")
      (footprint "YAGEO_0603_T0.55:RESC1608X06N")
      (description "RES 3.3K OHM 1% 1/10W 0603")
      (fields
        (field (name "MANUFACTURER") "Yageo")
        (field (name "MANUFACTURER PART NUMBER") "RC0603FR-073K3L")
      )
      (libsource (lib "PassiveComponents_Resistors_ChipSMD") (part "YAGEO_0603_T0.55"))
    )
    (comp (ref "R103")
      (value "330R")
      (footprint "YAGEO_0603_T0.55:RESC1608X06N")
      (description "RES 330 OHM 1% 1/10W 0603")
      (fields
        (field (name "MANUFACTURER") "Yageo")
        (field (name "MANUFACTURER PART NUMBER") "RC0603FR-07330RL")
      )
      (libsource (lib "PassiveComponents_Resistors_ChipSMD") (part "YAGEO_0603_T0.55"))
    )
    (comp (ref "R104")
      (value "0R")
      (footprint "YAGEO_0603_T0.55:RESC1608X06N")
      (description "RES 0 OHM JUMPER 1/10W 0603")
      (fields
        (field (name "MANUFACTURER") "Yageo")
        (field (name "MANUFACTURER PART NUMBER") "RC0603FR-070RL")
      )
      (libsource (lib "PassiveComponents_Resistors_ChipSMD") (part "YAGEO_0603_T0.55"))
    )
    (comp (ref "R105")
      (value "10K")
      (footprint "YAGEO_0603_T0.55:RESC1608X06N")
      (description "RES 10K OHM 1% 1/10W 0603")
      (fields
        (field (name "MANUFACTURER") "Yageo")
        (field (name "MANUFACTURER PART NUMBER") "RC0603FR-0710KL")
      )
      (libsource (lib "PassiveComponents_Resistors_ChipSMD") (part "YAGEO_0603_T0.55"))
    )
    (comp (ref "R106")
      (value "0R")
      (footprint "YAGEO_0603_T0.55:RESC1608X06N")
      (description "RES 0 OHM JUMPER 1/10W 0603")
      (fields
        (field (name "MANUFACTURER") "Yageo")
        (field (name "MANUFACTURER PART NUMBER") "RC0603FR-070RL")
      )
      (libsource (lib "PassiveComponents_Resistors_ChipSMD") (part "YAGEO_0603_T0.55"))
    )
    (comp (ref "SW1A")
      (value "SPST")
      (footprint "COPAL_CHS-02B")
      (description "SWITCH SLIDE DIP SPST 0.1A 6V")
      (fields (field (name "MANUFACTURER") "Nidec Copal") (field (name "MANUFACTURER PART NUMBER") "CHS-02B"))
      (libsource (lib "PassiveComponents_Switches") (part "COPAL_CHS-02B"))
    )
    (comp (ref "SW1B")
      (value "SPST")
      (footprint "COPAL_CHS-02B")
      (description "SWITCH SLIDE DIP SPST 0.1A 6V")
      (fields (field (name "MANUFACTURER") "Nidec Copal") (field (name "MANUFACTURER PART NUMBER") "CHS-02B"))
      (libsource (lib "PassiveComponents_Switches") (part "COPAL_CHS-02B"))
    )
    (comp (ref "TH1")
      (value "10K NTC 1%")
      (footprint "NETWORKER_THERMISTOR_2.54MM")
      (description "THER 10K 1% LEAD MMC SC25 (450103-006AQ)")
      (libsource (lib "CustomParts") (part "NETWORKER_THERMISTOR"))
    )
    (comp (ref "TP10")
      (value "TESTPOINT_OCTAGONAL")
      (footprint "TESTPOINT_OCTAGONAL")
      (libsource (lib "Miscellaneous") (part "TESTPOINT_OCTAGONAL"))
    )
    (comp (ref "TP11")
      (value "TESTPOINT_OCTAGONAL")
      (footprint "TESTPOINT_OCTAGONAL")
      (libsource (lib "Miscellaneous") (part "TESTPOINT_OCTAGONAL"))
    )
    (comp (ref "TP14")
      (value "TESTPOINT_OCTAGONAL")
      (footprint "TESTPOINT_OCTAGONAL")
      (libsource (lib "Miscellaneous") (part "TESTPOINT_OCTAGONAL"))
    )
    (comp (ref "TP15")
      (value "TESTPOINT_OCTAGONAL")
      (footprint "TESTPOINT_OCTAGONAL")
      (libsource (lib "Miscellaneous") (part "TESTPOINT_OCTAGONAL"))
    )
    (comp (ref "TP16")
      (value "TESTPOINT_OCTAGONAL")
      (footprint "TESTPOINT_OCTAGONAL")
      (libsource (lib "Miscellaneous") (part "TESTPOINT_OCTAGONAL"))
    )
    (comp (ref "TP17")
      (value "TESTPOINT_OCTAGONAL")
      (footprint "TESTPOINT_OCTAGONAL")
      (libsource (lib "Miscellaneous") (part "TESTPOINT_OCTAGONAL"))
    )
    (comp (ref "TP18")
      (value "TESTPOINT_OCTAGONAL")
      (footprint "TESTPOINT_OCTAGONAL")
      (libsource (lib "") (part "TESTPOINT_OCTAGONAL_3"))
    )
    (comp (ref "TP19")
      (value "TESTPOINT_OCTAGONAL")
      (footprint "TESTPOINT_OCTAGONAL")
      (libsource (lib "") (part "TESTPOINT_OCTAGONAL_2"))
    )
    (comp (ref "TP20")
      (value "TESTPOINT_OCTAGONAL")
      (footprint "TESTPOINT_OCTAGONAL")
      (libsource (lib "Miscellaneous") (part "TESTPOINT_OCTAGONAL"))
    )
    (comp (ref "TP21")
      (value "TESTPOINT_OCTAGONAL")
      (footprint "TESTPOINT_OCTAGONAL")
      (libsource (lib "Miscellaneous") (part "TESTPOINT_OCTAGONAL"))
    )
    (comp (ref "TP23")
      (value "TESTPOINT_OCTAGONAL")
      (footprint "TESTPOINT_OCTAGONAL")
      (libsource (lib "") (part "TESTPOINT_OCTAGONAL_2"))
    )
    (comp (ref "TP24")
      (value "TESTPOINT_OCTAGONAL")
      (footprint "TESTPOINT_OCTAGONAL")
      (libsource (lib "") (part "TESTPOINT_OCTAGONAL_2"))
    )
    (comp (ref "TP25")
      (value "TESTPOINT_OCTAGONAL")
      (footprint "TESTPOINT_OCTAGONAL")
      (libsource (lib "") (part "TESTPOINT_OCTAGONAL_2"))
    )
    (comp (ref "TP32")
      (value "TESTPOINT_OCTAGONAL")
      (footprint "TESTPOINT_OCTAGONAL")
      (libsource (lib "Miscellaneous") (part "TESTPOINT_OCTAGONAL"))
    )
    (comp (ref "TP34")
      (value "TESTPOINT_OCTAGONAL")
      (footprint "TESTPOINT_OCTAGONAL")
      (libsource (lib "Miscellaneous") (part "TESTPOINT_OCTAGONAL"))
    )
    (comp (ref "TP45")
      (value "TESTPOINT_OCTAGONAL")
      (footprint "TESTPOINT_OCTAGONAL")
      (libsource (lib "") (part "TESTPOINT_OCTAGONAL_3"))
    )
    (comp (ref "TP47")
      (value "TESTPOINT_OCTAGONAL")
      (footprint "TESTPOINT_OCTAGONAL")
      (libsource (lib "") (part "TESTPOINT_OCTAGONAL_3"))
    )
    (comp (ref "TP48")
      (value "TESTPOINT_OCTAGONAL")
      (footprint "TESTPOINT_OCTAGONAL")
      (libsource (lib "") (part "TESTPOINT_OCTAGONAL_3"))
    )
    (comp (ref "TP49")
      (value "TESTPOINT_OCTAGONAL")
      (footprint "TESTPOINT_OCTAGONAL")
      (libsource (lib "Miscellaneous") (part "TESTPOINT_OCTAGONAL"))
    )
    (comp (ref "TP56")
      (value "TESTPOINT_OCTAGONAL")
      (footprint "TESTPOINT_OCTAGONAL")
      (libsource (lib "") (part "TESTPOINT_OCTAGONAL_3"))
    )
    (comp (ref "TP57")
      (value "TESTPOINT_OCTAGONAL")
      (footprint "TESTPOINT_OCTAGONAL")
      (libsource (lib "") (part "TESTPOINT_OCTAGONAL_1"))
    )
    (comp (ref "TP58")
      (value "TESTPOINT_OCTAGONAL")
      (footprint "TESTPOINT_OCTAGONAL")
      (libsource (lib "Miscellaneous") (part "TESTPOINT_OCTAGONAL"))
    )
    (comp (ref "TP59")
      (value "TESTPOINT_OCTAGONAL")
      (footprint "TESTPOINT_OCTAGONAL")
      (libsource (lib "Miscellaneous") (part "TESTPOINT_OCTAGONAL"))
    )
    (comp (ref "TP60")
      (value "TESTPOINT_OCTAGONAL")
      (footprint "TESTPOINT_OCTAGONAL")
      (libsource (lib "") (part "TESTPOINT_OCTAGONAL_3"))
    )
    (comp (ref "TP61")
      (value "TESTPOINT_OCTAGONAL")
      (footprint "TESTPOINT_OCTAGONAL")
      (libsource (lib "Miscellaneous") (part "TESTPOINT_OCTAGONAL"))
    )
    (comp (ref "TP62")
      (value "TESTPOINT_OCTAGONAL")
      (footprint "TESTPOINT_OCTAGONAL")
      (libsource (lib "Miscellaneous") (part "TESTPOINT_OCTAGONAL"))
    )
    (comp (ref "TP63")
      (value "TESTPOINT_OCTAGONAL")
      (footprint "TESTPOINT_OCTAGONAL")
      (libsource (lib "") (part "TESTPOINT_OCTAGONAL_1"))
    )
    (comp (ref "TP64")
      (value "TESTPOINT_OCTAGONAL")
      (footprint "TESTPOINT_OCTAGONAL")
      (libsource (lib "Miscellaneous") (part "TESTPOINT_OCTAGONAL"))
    )
    (comp (ref "TP65")
      (value "TESTPOINT_OCTAGONAL")
      (footprint "TESTPOINT_OCTAGONAL")
      (libsource (lib "") (part "TESTPOINT_OCTAGONAL_1"))
    )
    (comp (ref "TP66")
      (value "TESTPOINT_OCTAGONAL")
      (footprint "TESTPOINT_OCTAGONAL")
      (libsource (lib "") (part "TESTPOINT_OCTAGONAL_1"))
    )
    (comp (ref "TP67")
      (value "TESTPOINT_OCTAGONAL")
      (footprint "TESTPOINT_OCTAGONAL")
      (libsource (lib "Miscellaneous") (part "TESTPOINT_OCTAGONAL"))
    )
    (comp (ref "TP68")
      (value "TESTPOINT_OCTAGONAL")
      (footprint "TESTPOINT_OCTAGONAL")
      (libsource (lib "") (part "TESTPOINT_OCTAGONAL_1"))
    )
    (comp (ref "TP69")
      (value "TESTPOINT_OCTAGONAL")
      (footprint "TESTPOINT_OCTAGONAL")
      (libsource (lib "") (part "TESTPOINT_OCTAGONAL_3"))
    )
    (comp (ref "TP70")
      (value "TESTPOINT_OCTAGONAL")
      (footprint "TESTPOINT_OCTAGONAL")
      (libsource (lib "Miscellaneous") (part "TESTPOINT_OCTAGONAL"))
    )
    (comp (ref "TP71")
      (value "TESTPOINT_OCTAGONAL")
      (footprint "TESTPOINT_OCTAGONAL")
      (libsource (lib "Miscellaneous") (part "TESTPOINT_OCTAGONAL"))
    )
    (comp (ref "TP72")
      (value "TESTPOINT_OCTAGONAL")
      (footprint "TESTPOINT_OCTAGONAL")
      (libsource (lib "") (part "TESTPOINT_OCTAGONAL_1"))
    )
    (comp (ref "TP73")
      (value "TESTPOINT_OCTAGONAL")
      (footprint "TESTPOINT_OCTAGONAL")
      (libsource (lib "") (part "TESTPOINT_OCTAGONAL_3"))
    )
    (comp (ref "TP74")
      (value "TESTPOINT_OCTAGONAL")
      (footprint "TESTPOINT_OCTAGONAL")
      (libsource (lib "Miscellaneous") (part "TESTPOINT_OCTAGONAL"))
    )
    (comp (ref "TP75")
      (value "TESTPOINT_OCTAGONAL")
      (footprint "TESTPOINT_OCTAGONAL")
      (libsource (lib "") (part "TESTPOINT_OCTAGONAL_1"))
    )
    (comp (ref "TP76")
      (value "TESTPOINT_OCTAGONAL")
      (footprint "TESTPOINT_OCTAGONAL")
      (libsource (lib "") (part "TESTPOINT_OCTAGONAL_2"))
    )
    (comp (ref "TP87")
      (value "TESTPOINT_OCTAGONAL")
      (footprint "TESTPOINT_OCTAGONAL")
      (libsource (lib "") (part "TESTPOINT_OCTAGONAL_3"))
    )
    (comp (ref "TP88")
      (value "TESTPOINT_OCTAGONAL")
      (footprint "TESTPOINT_OCTAGONAL")
      (libsource (lib "Miscellaneous") (part "TESTPOINT_OCTAGONAL"))
    )
    (comp (ref "TP89")
      (value "TESTPOINT_OCTAGONAL")
      (footprint "TESTPOINT_OCTAGONAL")
      (libsource (lib "") (part "TESTPOINT_OCTAGONAL_3"))
    )
    (comp (ref "TP92")
      (value "TESTPOINT_OCTAGONAL")
      (footprint "TESTPOINT_OCTAGONAL")
      (libsource (lib "") (part "TESTPOINT_OCTAGONAL_3"))
    )
    (comp (ref "TP93")
      (value "TESTPOINT_OCTAGONAL")
      (footprint "TESTPOINT_OCTAGONAL")
      (libsource (lib "") (part "TESTPOINT_OCTAGONAL_3"))
    )
    (comp (ref "TP94")
      (value "TESTPOINT_OCTAGONAL")
      (footprint "TESTPOINT_OCTAGONAL")
      (libsource (lib "") (part "TESTPOINT_OCTAGONAL_3"))
    )
    (comp (ref "TP95")
      (value "TESTPOINT_OCTAGONAL")
      (footprint "TESTPOINT_OCTAGONAL")
      (libsource (lib "") (part "TESTPOINT_OCTAGONAL_3"))
    )
    (comp (ref "TP96")
      (value "TESTPOINT_OCTAGONAL")
      (footprint "TESTPOINT_OCTAGONAL")
      (libsource (lib "") (part "TESTPOINT_OCTAGONAL_3"))
    )
    (comp (ref "TP97")
      (value "TESTPOINT_OCTAGONAL")
      (footprint "TESTPOINT_OCTAGONAL")
      (libsource (lib "") (part "TESTPOINT_OCTAGONAL_3"))
    )
    (comp (ref "TP98")
      (value "TESTPOINT_OCTAGONAL")
      (footprint "TESTPOINT_OCTAGONAL")
      (libsource (lib "") (part "TESTPOINT_OCTAGONAL_3"))
    )
    (comp (ref "TP102")
      (value "TESTPOINT_OCTAGONAL")
      (footprint "TESTPOINT_OCTAGONAL")
      (libsource (lib "") (part "TESTPOINT_OCTAGONAL_2"))
    )
    (comp (ref "TP103")
      (value "TESTPOINT_OCTAGONAL")
      (footprint "TESTPOINT_OCTAGONAL")
      (libsource (lib "") (part "TESTPOINT_OCTAGONAL_2"))
    )
    (comp (ref "TP104")
      (value "TESTPOINT_OCTAGONAL")
      (footprint "TESTPOINT_OCTAGONAL")
      (libsource (lib "") (part "TESTPOINT_OCTAGONAL_2"))
    )
    (comp (ref "TP105")
      (value "TESTPOINT_OCTAGONAL")
      (footprint "TESTPOINT_OCTAGONAL")
      (libsource (lib "") (part "TESTPOINT_OCTAGONAL_2"))
    )
    (comp (ref "TP106")
      (value "TESTPOINT_OCTAGONAL")
      (footprint "TESTPOINT_OCTAGONAL")
      (libsource (lib "") (part "TESTPOINT_OCTAGONAL_3"))
    )
    (comp (ref "TP107")
      (value "TESTPOINT_OCTAGONAL")
      (footprint "TESTPOINT_OCTAGONAL")
      (libsource (lib "") (part "TESTPOINT_OCTAGONAL_3"))
    )
    (comp (ref "TP108")
      (value "TESTPOINT_OCTAGONAL")
      (footprint "TESTPOINT_OCTAGONAL")
      (libsource (lib "") (part "TESTPOINT_OCTAGONAL_3"))
    )
    (comp (ref "TP109")
      (value "TESTPOINT_OCTAGONAL")
      (footprint "TESTPOINT_OCTAGONAL")
      (libsource (lib "") (part "TESTPOINT_OCTAGONAL_3"))
    )
    (comp (ref "TP110")
      (value "TESTPOINT_OCTAGONAL")
      (footprint "TESTPOINT_OCTAGONAL")
      (libsource (lib "") (part "TESTPOINT_OCTAGONAL_3"))
    )
    (comp (ref "TP111")
      (value "TESTPOINT_OCTAGONAL")
      (footprint "TESTPOINT_OCTAGONAL")
      (libsource (lib "") (part "TESTPOINT_OCTAGONAL_3"))
    )
    (comp (ref "TP112")
      (value "TESTPOINT_OCTAGONAL")
      (footprint "TESTPOINT_OCTAGONAL")
      (libsource (lib "") (part "TESTPOINT_OCTAGONAL_3"))
    )
    (comp (ref "TP113")
      (value "TESTPOINT_OCTAGONAL")
      (footprint "TESTPOINT_OCTAGONAL")
      (libsource (lib "") (part "TESTPOINT_OCTAGONAL_3"))
    )
    (comp (ref "TP114")
      (value "TESTPOINT_OCTAGONAL")
      (footprint "TESTPOINT_OCTAGONAL")
      (libsource (lib "") (part "TESTPOINT_OCTAGONAL_3"))
    )
    (comp (ref "TP115")
      (value "TESTPOINT_OCTAGONAL")
      (footprint "TESTPOINT_OCTAGONAL")
      (libsource (lib "Miscellaneous") (part "TESTPOINT_OCTAGONAL"))
    )
    (comp (ref "TP116")
      (value "TESTPOINT_OCTAGONAL")
      (footprint "TESTPOINT_OCTAGONAL")
      (libsource (lib "Miscellaneous") (part "TESTPOINT_OCTAGONAL"))
    )
    (comp (ref "TP117")
      (value "TESTPOINT_OCTAGONAL")
      (footprint "TESTPOINT_OCTAGONAL")
      (libsource (lib "Miscellaneous") (part "TESTPOINT_OCTAGONAL"))
    )
    (comp (ref "TP118")
      (value "TESTPOINT_OCTAGONAL")
      (footprint "TESTPOINT_OCTAGONAL")
      (libsource (lib "Miscellaneous") (part "TESTPOINT_OCTAGONAL"))
    )
    (comp (ref "TP119")
      (value "TESTPOINT_OCTAGONAL")
      (footprint "TESTPOINT_OCTAGONAL")
      (libsource (lib "Miscellaneous") (part "TESTPOINT_OCTAGONAL"))
    )
    (comp (ref "TP120")
      (value "TESTPOINT_OCTAGONAL")
      (footprint "TESTPOINT_OCTAGONAL")
      (libsource (lib "Miscellaneous") (part "TESTPOINT_OCTAGONAL"))
    )
    (comp (ref "TP121")
      (value "TESTPOINT_OCTAGONAL")
      (footprint "TESTPOINT_OCTAGONAL")
      (libsource (lib "Miscellaneous") (part "TESTPOINT_OCTAGONAL"))
    )
    (comp (ref "TP122")
      (value "TESTPOINT_OCTAGONAL")
      (footprint "TESTPOINT_OCTAGONAL")
      (libsource (lib "Miscellaneous") (part "TESTPOINT_OCTAGONAL"))
    )
    (comp (ref "TP180")
      (value "TESTPOINT_OCTAGONAL")
      (footprint "TESTPOINT_OCTAGONAL")
      (libsource (lib "") (part "TESTPOINT_OCTAGONAL_1"))
    )
    (comp (ref "TP181")
      (value "TESTPOINT_OCTAGONAL")
      (footprint "TESTPOINT_OCTAGONAL")
      (libsource (lib "") (part "TESTPOINT_OCTAGONAL_2"))
    )
    (comp (ref "TP182")
      (value "TESTPOINT_OCTAGONAL")
      (footprint "TESTPOINT_OCTAGONAL")
      (libsource (lib "") (part "TESTPOINT_OCTAGONAL_1"))
    )
    (comp (ref "TP183")
      (value "TESTPOINT_OCTAGONAL")
      (footprint "TESTPOINT_OCTAGONAL")
      (libsource (lib "") (part "TESTPOINT_OCTAGONAL_1"))
    )
    (comp (ref "TP188")
      (value "TESTPOINT_OCTAGONAL")
      (footprint "TESTPOINT_OCTAGONAL")
      (libsource (lib "") (part "TESTPOINT_OCTAGONAL_3"))
    )
    (comp (ref "TP189")
      (value "TESTPOINT_OCTAGONAL")
      (footprint "TESTPOINT_OCTAGONAL")
      (libsource (lib "") (part "TESTPOINT_OCTAGONAL_1"))
    )
    (comp (ref "TP190")
      (value "TESTPOINT_OCTAGONAL")
      (footprint "TESTPOINT_OCTAGONAL")
      (libsource (lib "Miscellaneous") (part "TESTPOINT_OCTAGONAL"))
    )
    (comp (ref "TP191")
      (value "TESTPOINT_ROUND")
      (footprint "TESTPOINT_ROUND")
      (libsource (lib "Miscellaneous") (part "TESTPOINT_ROUND"))
    )
    (comp (ref "U1")
      (value "STM32F103RG")
      (footprint "STM_STM32F103RG_LQFP64:TSQFP50P1200X1200X160-64N")
      (description "IC MCU 32BIT 1MB FLASH 64LQFP")
      (fields
        (field (name "MANUFACTURER") "STMicroelectronics")
        (field (name "MANUFACTURER PART NUMBER") "STM32F103RGT6")
      )
      (libsource (lib "IntegratedCircuits_Embedded_Microcontrollers") (part "STM_STM32F103RG_LQFP64"))
    )
    (comp (ref "U2")
      (value "M24M02")
      (footprint "STM_M24M02-DR_SOIC8:SOIC127P600X175-8N")
      (description "IC EEPROM 2MBIT I2C 1MHZ 8SO")
      (fields
        (field (name "MANUFACTURER") "STMicroelectronics")
        (field (name "MANUFACTURER PART NUMBER") "M24M02-DRMN6TP")
      )
      (libsource (lib "IntegratedCircuits_Memory_EEPROM") (part "STM_M24M02-DR_SOIC8"))
    )
    (comp (ref "U3")
      (value "M24M02")
      (footprint "STM_M24M02-DR_SOIC8:SOIC127P600X175-8N")
      (description "IC EEPROM 2MBIT I2C 1MHZ 8SO")
      (fields
        (field (name "MANUFACTURER") "STMicroelectronics")
        (field (name "MANUFACTURER PART NUMBER") "M24M02-DRMN6TP")
      )
      (libsource (lib "IntegratedCircuits_Memory_EEPROM") (part "STM_M24M02-DR_SOIC8"))
    )
    (comp (ref "U5")
      (value "SP6205EM5-L")
      (footprint "EXAR_SP6205EM5-L_SOT23_5:SOT95P280X145-5N")
      (description "IC REG LIN POS ADJ 500MA SOT23-5")
      (fields (field (name "MANUFACTURER") "Exar") (field (name "MANUFACTURER PART NUMBER") "SP6205EM5-L/TR"))
      (libsource (lib "IntegratedCircuits_Power_VoltageRegsLinear") (part "EXAR_SP6205EM5-L_SOT23_5"))
    )
    (comp (ref "U6")
      (value "SP6205EM5-L")
      (footprint "EXAR_SP6205EM5-L_SOT23_5:SOT95P280X145-5N")
      (description "IC REG LIN POS ADJ 500MA SOT23-5")
      (fields (field (name "MANUFACTURER") "Exar") (field (name "MANUFACTURER PART NUMBER") "SP6205EM5-L/TR"))
      (libsource (lib "IntegratedCircuits_Power_VoltageRegsLinear") (part "EXAR_SP6205EM5-L_SOT23_5"))
    )
    (comp (ref "U7")
      (value "FT230XS")
      (footprint "FTDI_FT230XS_SOP64P600X175-16N")
      (description "IC USB SERIAL BASIC UART 16SSOP")
      (fields (field (name "MANUFACTURER") "FTDI") (field (name "MANUFACTURER PART NUMBER") "FT230XS-U"))
      (libsource (lib "IntegratedCircuits_Interface_RSType") (part "FTDI_FT230XS_SSOP16"))
    )
    (comp (ref "U35")
      (value "TLV75533PDBVR")
      (footprint "TI_TLV75533PDBVR_SOT23_5:SOT95P280X145-5N")
      (description "IC REG LINEAR 3.3V 500MA SOT23-5")
      (fields (field (name "MANUFACTURER") "Texas Instruments"))
      (libsource (lib "IntegratedCircuits_Power_VoltageRegsLinear") (part "TI_TLV75533PDBVR_SOT23_5"))
    )
    (comp (ref "V1")
      (value "5V Cont / 150V Trip")
      (footprint "BOURNS_CGA0603MLC:INDC1608X04N")
      (description "VARISTOR 0603")
      (fields
        (field (name "MANUFACTURER") "Bourns")
        (field (name "MANUFACTURER PART NUMBER") "CG0603MLC-05E")
      )
      (libsource (lib "CircuitProtection_Varistors") (part "BOURNS_CGA0603MLC"))
    )
    (comp (ref "V2")
      (value "5V Cont / 150V Trip")
      (footprint "BOURNS_CGA0603MLC:INDC1608X04N")
      (description "VARISTOR 0603")
      (fields
        (field (name "MANUFACTURER") "Bourns")
        (field (name "MANUFACTURER PART NUMBER") "CG0603MLC-05E")
      )
      (libsource (lib "CircuitProtection_Varistors") (part "BOURNS_CGA0603MLC"))
    )
    (comp (ref "V3")
      (value "5V Cont / 150V Trip")
      (footprint "BOURNS_CGA0603MLC:INDC1608X04N")
      (description "VARISTOR 0603")
      (fields
        (field (name "MANUFACTURER") "Bourns")
        (field (name "MANUFACTURER PART NUMBER") "CG0603MLC-05E")
      )
      (libsource (lib "CircuitProtection_Varistors") (part "BOURNS_CGA0603MLC"))
    )
    (comp (ref "X1")
      (value "8MHz")
      (footprint "MURATA_CSTNE8M00G550000R0")
      (description "CERAMIC RES 8.0000MHZ 33PF SMD")
      (fields
        (field (name "MANUFACTURER") "Murata")
        (field (name "MANUFACTURER PART NUMBER") "CSTNE8M00G550000R0")
      )
      (libsource (lib "PassiveComponents_Oscillators_Resonators") (part "MURATA_CSTNE8M00G550000R0"))
    )
    (comp (ref "X3")
      (value "32768Hz")
      (footprint "EPSON_MC-146")
      (description "CRYSTAL 32.7680KHZ 12.5PF SMD")
      (fields
        (field (name "MANUFACTURER") "Epson")
        (field (name "MANUFACTURER PART NUMBER") "MC-14632.7680KA-A0:ROHS")
      )
      (libsource (lib "PassiveComponents_Oscillators_Resonators") (part "EPSON_MC-146"))
    )
  )
  (nets
    (net (code "1") (name "/5VUSB_CON") (class "Default")
      (node (ref "M1") (pin "A9") (pinfunction "CC_IO12_SPARE_A9") (pintype "passive"))
      (node (ref "Q6") (pin "1") (pinfunction "G_1") (pintype "passive"))
      (node (ref "R20") (pin "2") (pinfunction "2_2") (pintype "passive"))
      (node (ref "TP32") (pin "1") (pinfunction "1_1") (pintype "passive"))
      (node (ref "U1") (pin "9") (pinfunction "PC1_9") (pintype "bidirectional"))
    )
    (net (code "2") (name "/10ms") (class "Default")
      (node (ref "TP191") (pin "1") (pinfunction "1_1") (pintype "passive"))
      (node (ref "U1") (pin "40") (pinfunction "PC9_40") (pintype "bidirectional"))
    )
    (net (code "3") (name "/AP_MODE") (class "Default")
      (node (ref "M1") (pin "C11") (pinfunction "AP_MODE_C11") (pintype "passive"))
      (node (ref "TP112") (pin "1") (pinfunction "1_1") (pintype "passive"))
      (node (ref "U1") (pin "61") (pinfunction "PB8_61") (pintype "bidirectional"))
    )
    (net (code "4") (name "/BOOT0") (class "Default")
      (node (ref "R3") (pin "2") (pinfunction "2_2") (pintype "passive"))
      (node (ref "SW1A") (pin "2") (pinfunction "2_2") (pintype "passive"))
      (node (ref "TP48") (pin "1") (pinfunction "1_1") (pintype "passive"))
      (node (ref "U1") (pin "60") (pinfunction "BOOT_60") (pintype "passive"))
    )
    (net (code "5") (name "/BOOT1") (class "Default")
      (node (ref "R4") (pin "1") (pinfunction "1_1") (pintype "passive"))
      (node (ref "SW1B") (pin "1") (pinfunction "1_1") (pintype "passive"))
      (node (ref "TP19") (pin "1") (pinfunction "1_1") (pintype "passive"))
      (node (ref "U1") (pin "28") (pinfunction "PB2_28") (pintype "bidirectional"))
    )
    (net (code "6") (name "/CC_IO00_SPARE") (class "Default")
      (node (ref "M1") (pin "C10") (pinfunction "CC_IO00_SPARE_C10") (pintype "passive"))
      (node (ref "TP98") (pin "1") (pinfunction "1_1") (pintype "passive"))
      (node (ref "U1") (pin "8") (pinfunction "PC0_8") (pintype "bidirectional"))
    )
    (net (code "7") (name "/CC_IO03_SPARE") (class "Default")
      (node (ref "M1") (pin "C7") (pinfunction "CC_IO03_SPARE_C7") (pintype "passive"))
      (node (ref "TP97") (pin "1") (pinfunction "1_1") (pintype "passive"))
      (node (ref "U1") (pin "15") (pinfunction "PA1_15") (pintype "bidirectional"))
    )
    (net (code "8") (name "/CC_IO04_SPARE") (class "Default")
      (node (ref "M1") (pin "C6") (pinfunction "CC_IO04_SPARE_C6") (pintype "passive"))
      (node (ref "TP96") (pin "1") (pinfunction "1_1") (pintype "passive"))
      (node (ref "U1") (pin "29") (pinfunction "PB10_29") (pintype "bidirectional"))
    )
    (net (code "9") (name "/CC_IO05_SPARE") (class "Default")
      (node (ref "M1") (pin "C5") (pinfunction "CC_IO05_SPARE_C5") (pintype "passive"))
      (node (ref "TP95") (pin "1") (pinfunction "1_1") (pintype "passive"))
      (node (ref "U1") (pin "30") (pinfunction "PB11_30") (pintype "bidirectional"))
    )
    (net (code "10") (name "/CC_IO06_SPARE") (class "Default")
      (node (ref "M1") (pin "C4") (pinfunction "CC_IO06_SPARE_C4") (pintype "passive"))
      (node (ref "TP94") (pin "1") (pinfunction "1_1") (pintype "passive"))
      (node (ref "U1") (pin "45") (pinfunction "PA12_45") (pintype "bidirectional"))
    )
    (net (code "11") (name "/CC_IO08_SPARE") (class "Default")
      (node (ref "M1") (pin "C2") (pinfunction "CC_IO08_SPARE_C2") (pintype "passive"))
      (node (ref "TP93") (pin "1") (pinfunction "1_1") (pintype "passive"))
      (node (ref "U1") (pin "44") (pinfunction "PA11_44") (pintype "bidirectional"))
    )
    (net (code "12") (name "/CC_IO09_SPARE") (class "Default")
      (node (ref "M1") (pin "C1") (pinfunction "CC_IO09_SPARE_C1") (pintype "passive"))
      (node (ref "TP92") (pin "1") (pinfunction "1_1") (pintype "passive"))
      (node (ref "U1") (pin "41") (pinfunction "PA8_41") (pintype "bidirectional"))
    )
    (net (code "13") (name "/CC_IO22_SPARE") (class "Default")
      (node (ref "M1") (pin "A11") (pinfunction "CC_IO22_SPARE_A11") (pintype "passive"))
      (node (ref "TP89") (pin "1") (pinfunction "1_1") (pintype "passive"))
      (node (ref "U1") (pin "52") (pinfunction "PC11_52") (pintype "bidirectional"))
    )
    (net (code "14") (name "/CC_IO28_SPARE") (class "Default")
      (node (ref "M1") (pin "B2") (pinfunction "CC_IO28_SPARE_B2") (pintype "passive"))
      (node (ref "TP88") (pin "1") (pinfunction "1_1") (pintype "passive"))
      (node (ref "U1") (pin "51") (pinfunction "PC10_51") (pintype "bidirectional"))
    )
    (net (code "15") (name "/CC_JTAG_TCK") (class "Default")
      (node (ref "CN1W") (pin "9") (pinfunction "9_9") (pintype "passive"))
      (node (ref "M1") (pin "B3") (pinfunction "CC_JTAG_TCK_B3") (pintype "passive"))
      (node (ref "TP121") (pin "1") (pinfunction "1_1") (pintype "passive"))
    )
    (net (code "16") (name "/CC_JTAG_TDI") (class "Default")
      (node (ref "CN1W") (pin "2") (pinfunction "2_2") (pintype "passive"))
      (node (ref "M1") (pin "A12") (pinfunction "CC_JTAG_TDI_A12") (pintype "passive"))
      (node (ref "TP115") (pin "1") (pinfunction "1_1") (pintype "passive"))
    )
    (net (code "17") (name "/CC_JTAG_TDO") (class "Default")
      (node (ref "CN1W") (pin "4") (pinfunction "4_4") (pintype "passive"))
      (node (ref "M1") (pin "B1") (pinfunction "CC_JTAG_TDO_B1") (pintype "passive"))
      (node (ref "TP117") (pin "1") (pinfunction "1_1") (pintype "passive"))
    )
    (net (code "18") (name "/CC_JTAG_TMS") (class "Default")
      (node (ref "CN1W") (pin "3") (pinfunction "3_3") (pintype "passive"))
      (node (ref "M1") (pin "B4") (pinfunction "CC_JTAG_TMS_B4") (pintype "passive"))
      (node (ref "TP116") (pin "1") (pinfunction "1_1") (pintype "passive"))
    )
    (net (code "19") (name "/CC_PGM") (class "Default")
      (node (ref "CN1W") (pin "8") (pinfunction "8_8") (pintype "passive"))
      (node (ref "M1") (pin "B5") (pinfunction "CC_PGM_B5") (pintype "passive"))
      (node (ref "TP120") (pin "1") (pinfunction "1_1") (pintype "passive"))
      (node (ref "U1") (pin "11") (pinfunction "PC3_11") (pintype "bidirectional"))
    )
    (net (code "20") (name "/CC_RST#") (class "Default")
      (node (ref "CN1W") (pin "6") (pinfunction "6_6") (pintype "passive"))
      (node (ref "M1") (pin "C12") (pinfunction "CC_RST#_C12") (pintype "passive"))
      (node (ref "R103") (pin "1") (pinfunction "1_1") (pintype "passive"))
      (node (ref "TP119") (pin "1") (pinfunction "1_1") (pintype "passive"))
    )
    (net (code "21") (name "/CC_SWD") (class "Default")
      (node (ref "M1") (pin "C13") (pinfunction "CC_SWD_C13") (pintype "passive"))
      (node (ref "TP114") (pin "1") (pinfunction "1_1") (pintype "passive"))
      (node (ref "U1") (pin "10") (pinfunction "PC2_10") (pintype "bidirectional"))
    )
    (net (code "22") (name "/EEP_WC#") (class "Default")
      (node (ref "M1") (pin "C3") (pinfunction "EXT_EEP_WC#_C3") (pintype "passive"))
      (node (ref "R9") (pin "1") (pinfunction "1_1") (pintype "passive"))
      (node (ref "TP25") (pin "1") (pinfunction "1_1") (pintype "passive"))
      (node (ref "U1") (pin "14") (pinfunction "PA0-WKUP_14") (pintype "bidirectional"))
      (node (ref "U2") (pin "7") (pinfunction "~{WC}_7") (pintype "input"))
      (node (ref "U3") (pin "7") (pinfunction "~{WC}_7") (pintype "input"))
    )
    (net (code "23") (name "/FT800_CS#") (class "Default")
      (node (ref "U1") (pin "24") (pinfunction "PC4_24") (pintype "bidirectional"))
    )
    (net (code "24") (name "/FT800_INT#") (class "Default")
      (node (ref "U1") (pin "20") (pinfunction "PA4_20") (pintype "bidirectional"))
    )
    (net (code "25") (name "/FT800_MISO") (class "Default")
      (node (ref "U1") (pin "22") (pinfunction "PA6_22") (pintype "bidirectional"))
    )
    (net (code "26") (name "/FT800_MOSI") (class "Default")
      (node (ref "U1") (pin "23") (pinfunction "PA7_23") (pintype "bidirectional"))
    )
    (net (code "27") (name "/FT800_PD#") (class "Default")
      (node (ref "U1") (pin "25") (pinfunction "PC5_25") (pintype "bidirectional"))
    )
    (net (code "28") (name "/FT800_SCK") (class "Default")
      (node (ref "U1") (pin "21") (pinfunction "PA5_21") (pintype "bidirectional"))
    )
    (net (code "29") (name "/FTDI_RX") (class "Default")
      (node (ref "CN1W") (pin "5") (pinfunction "5_5") (pintype "passive"))
      (node (ref "M1") (pin "C9") (pinfunction "FTDI_RX_C9") (pintype "passive"))
      (node (ref "TP118") (pin "1") (pinfunction "1_1") (pintype "passive"))
    )
    (net (code "30") (name "/FTDI_TX") (class "Default")
      (node (ref "CN1W") (pin "10") (pinfunction "10_10") (pintype "passive"))
      (node (ref "M1") (pin "C8") (pinfunction "FTDI_TX_C8") (pintype "passive"))
      (node (ref "TP122") (pin "1") (pinfunction "1_1") (pintype "passive"))
    )
    (net (code "31") (name "/I2C_SCL") (class "Default")
      (node (ref "CN1S") (pin "10") (pinfunction "10_10") (pintype "passive"))
      (node (ref "M1") (pin "A3") (pinfunction "EXT_I2C_SCL_A3") (pintype "passive"))
      (node (ref "R8") (pin "1") (pinfunction "1_1") (pintype "passive"))
      (node (ref "TP23") (pin "1") (pinfunction "1_1") (pintype "passive"))
      (node (ref "U1") (pin "58") (pinfunction "PB6_58") (pintype "bidirectional"))
      (node (ref "U2") (pin "6") (pinfunction "SCL_6") (pintype "open_collector"))
      (node (ref "U3") (pin "6") (pinfunction "SCL_6") (pintype "open_collector"))
    )
    (net (code "32") (name "/I2C_SDA") (class "Default")
      (node (ref "CN1S") (pin "5") (pinfunction "5_5") (pintype "passive"))
      (node (ref "M1") (pin "A4") (pinfunction "EXT_I2C_SDA_A4") (pintype "passive"))
      (node (ref "R7") (pin "1") (pinfunction "1_1") (pintype "passive"))
      (node (ref "TP24") (pin "1") (pinfunction "1_1") (pintype "passive"))
      (node (ref "U1") (pin "59") (pinfunction "PB7_59") (pintype "bidirectional"))
      (node (ref "U2") (pin "5") (pinfunction "SDA_5") (pintype "open_collector"))
      (node (ref "U3") (pin "5") (pinfunction "SDA_5") (pintype "open_collector"))
    )
    (net (code "33") (name "/MON_12VPWR") (class "Default")
      (node (ref "M1") (pin "A10") (pinfunction "CC_IO13_SPARE_A10") (pintype "passive"))
      (node (ref "R14") (pin "1") (pinfunction "1_1") (pintype "passive"))
      (node (ref "R15") (pin "2") (pinfunction "2_2") (pintype "passive"))
      (node (ref "TP34") (pin "1") (pinfunction "1_1") (pintype "passive"))
      (node (ref "U1") (pin "2") (pinfunction "PC13-TAMPER/RTC_2") (pintype "bidirectional"))
    )
    (net (code "34") (name "/PWREN#") (class "Default")
      (node (ref "R23") (pin "1") (pinfunction "1_1") (pintype "passive"))
      (node (ref "TP65") (pin "1") (pinfunction "1_1") (pintype "passive"))
      (node (ref "U7") (pin "16") (pinfunction "CBUS3_16") (pintype "passive"))
    )
    (net (code "35") (name "/ST_JTAG_TCK") (class "Default")
      (node (ref "CN1S") (pin "9") (pinfunction "9_9") (pintype "passive"))
      (node (ref "TP15") (pin "1") (pinfunction "1_1") (pintype "passive"))
      (node (ref "U1") (pin "49") (pinfunction "PA14_49") (pintype "bidirectional"))
    )
    (net (code "36") (name "/ST_JTAG_TDI") (class "Default")
      (node (ref "CN1S") (pin "8") (pinfunction "8_8") (pintype "passive"))
      (node (ref "TP16") (pin "1") (pinfunction "1_1") (pintype "passive"))
      (node (ref "U1") (pin "50") (pinfunction "PA15_50") (pintype "bidirectional"))
    )
    (net (code "37") (name "/ST_JTAG_TDO") (class "Default")
      (node (ref "CN1S") (pin "4") (pinfunction "4_4") (pintype "passive"))
      (node (ref "TP20") (pin "1") (pinfunction "1_1") (pintype "passive"))
      (node (ref "U1") (pin "55") (pinfunction "PB3_55") (pintype "bidirectional"))
    )
    (net (code "38") (name "/ST_JTAG_TMS") (class "Default")
      (node (ref "CN1S") (pin "3") (pinfunction "3_3") (pintype "passive"))
      (node (ref "TP14") (pin "1") (pinfunction "1_1") (pintype "passive"))
      (node (ref "U1") (pin "46") (pinfunction "PA13_46") (pintype "bidirectional"))
    )
    (net (code "39") (name "/ST_JTAG_TRST#") (class "Default")
      (node (ref "CN1S") (pin "2") (pinfunction "2_2") (pintype "passive"))
      (node (ref "TP21") (pin "1") (pinfunction "1_1") (pintype "passive"))
      (node (ref "U1") (pin "56") (pinfunction "PB4_56") (pintype "bidirectional"))
    )
    (net (code "40") (name "/ST_RST#") (class "Default")
      (node (ref "C8") (pin "2") (pinfunction "2_2") (pintype "passive"))
      (node (ref "CN1S") (pin "6") (pinfunction "6_6") (pintype "passive"))
      (node (ref "TP49") (pin "1") (pinfunction "1_1") (pintype "passive"))
      (node (ref "U1") (pin "7") (pinfunction "NRST_7") (pintype "bidirectional"))
    )
    (net (code "41") (name "/ST_SPI2_MISO") (class "Default")
      (node (ref "R82") (pin "2") (pinfunction "2_2") (pintype "passive"))
      (node (ref "TP107") (pin "1") (pinfunction "1_1") (pintype "passive"))
      (node (ref "U1") (pin "34") (pinfunction "PB13_34") (pintype "bidirectional"))
    )
    (net (code "42") (name "/ST_SPI2_MOSI") (class "Default")
      (node (ref "R81") (pin "2") (pinfunction "2_2") (pintype "passive"))
      (node (ref "TP108") (pin "1") (pinfunction "1_1") (pintype "passive"))
      (node (ref "U1") (pin "33") (pinfunction "PB12_33") (pintype "bidirectional"))
    )
    (net (code "43") (name "/ST_SPI2_NSS") (class "Default")
      (node (ref "R79") (pin "2") (pinfunction "2_2") (pintype "passive"))
      (node (ref "TP110") (pin "1") (pinfunction "1_1") (pintype "passive"))
      (node (ref "U1") (pin "36") (pinfunction "PB15_36") (pintype "bidirectional"))
    )
    (net (code "44") (name "/ST_SPI2_SCK") (class "Default")
      (node (ref "R83") (pin "2") (pinfunction "2_2") (pintype "passive"))
      (node (ref "TP106") (pin "1") (pinfunction "1_1") (pintype "passive"))
      (node (ref "U1") (pin "35") (pinfunction "PB14_35") (pintype "bidirectional"))
    )
    (net (code "45") (name "/ST_UART2_RX") (class "Default")
      (node (ref "R80") (pin "2") (pinfunction "2_2") (pintype "passive"))
      (node (ref "TP109") (pin "1") (pinfunction "1_1") (pintype "passive"))
      (node (ref "U1") (pin "17") (pinfunction "PA3_17") (pintype "bidirectional"))
    )
    (net (code "46") (name "/ST_UART2_TX") (class "Default")
      (node (ref "R78") (pin "2") (pinfunction "2_2") (pintype "passive"))
      (node (ref "TP111") (pin "1") (pinfunction "1_1") (pintype "passive"))
      (node (ref "U1") (pin "16") (pinfunction "PA2_16") (pintype "bidirectional"))
    )
    (net (code "47") (name "/THM_MES") (class "Default")
      (node (ref "C12") (pin "2") (pinfunction "2_2") (pintype "passive"))
      (node (ref "R5") (pin "2") (pinfunction "2_2") (pintype "passive"))
      (node (ref "TH1") (pin "1") (pinfunction "1_1") (pintype "passive"))
      (node (ref "TP18") (pin "1") (pinfunction "1_1") (pintype "passive"))
      (node (ref "U1") (pin "27") (pinfunction "PB1_27") (pintype "bidirectional"))
    )
    (net (code "48") (name "/TWB_PWR") (class "Default")
      (node (ref "U1") (pin "38") (pinfunction "PC7_38") (pintype "bidirectional"))
    )
    (net (code "49") (name "/TWB_RX") (class "Default")
      (node (ref "U1") (pin "54") (pinfunction "PD2_54") (pintype "bidirectional"))
    )
    (net (code "50") (name "/TWB_TX") (class "Default")
      (node (ref "U1") (pin "53") (pinfunction "PC12_53") (pintype "bidirectional"))
    )
    (net (code "51") (name "/USB_RX") (class "Default")
      (node (ref "TP10") (pin "1") (pinfunction "1_1") (pintype "passive"))
      (node (ref "U1") (pin "42") (pinfunction "PA9_42") (pintype "bidirectional"))
      (node (ref "U7") (pin "4") (pinfunction "RxD_4") (pintype "passive"))
    )
    (net (code "52") (name "/USB_TX") (class "Default")
      (node (ref "TP11") (pin "1") (pinfunction "1_1") (pintype "passive"))
      (node (ref "U1") (pin "43") (pinfunction "PA10_43") (pintype "bidirectional"))
      (node (ref "U7") (pin "1") (pinfunction "TxD_1") (pintype "passive"))
    )
    (net (code "53") (name "/Vddmes") (class "Default")
      (node (ref "TH1") (pin "2") (pinfunction "2_2") (pintype "passive"))
      (node (ref "TP17") (pin "1") (pinfunction "1_1") (pintype "passive"))
      (node (ref "U1") (pin "26") (pinfunction "PB0_26") (pintype "bidirectional"))
    )
    (net (code "54") (name "/WIFI_DETECT") (class "Default")
      (node (ref "M1") (pin "C18") (pinfunction "DETECT-OT_C18") (pintype "passive"))
      (node (ref "R105") (pin "2") (pinfunction "2_2") (pintype "passive"))
      (node (ref "TP189") (pin "1") (pinfunction "1_1") (pintype "passive"))
      (node (ref "U1") (pin "37") (pinfunction "PC6_37") (pintype "bidirectional"))
    )
    (net (code "55") (name "/WIFI_PWR") (class "Default")
      (node (ref "R101") (pin "1") (pinfunction "1_1") (pintype "passive"))
      (node (ref "R102") (pin "1") (pinfunction "1_1") (pintype "passive"))
      (node (ref "TP113") (pin "1") (pinfunction "1_1") (pintype "passive"))
      (node (ref "U1") (pin "62") (pinfunction "PB9_62") (pintype "bidirectional"))
    )
    (net (code "56") (name "3V3") (class "Default")
      (node (ref "C1") (pin "1") (pinfunction "1_1") (pintype "passive"))
      (node (ref "C10") (pin "1") (pinfunction "1_1") (pintype "passive"))
      (node (ref "C13") (pin "2") (pinfunction "2_2") (pintype "passive"))
      (node (ref "C14") (pin "2") (pinfunction "2_2") (pintype "passive"))
      (node (ref "C2") (pin "1") (pinfunction "1_1") (pintype "passive"))
      (node (ref "C3") (pin "1") (pinfunction "1_1") (pintype "passive"))
      (node (ref "C4") (pin "1") (pinfunction "1_1") (pintype "passive"))
      (node (ref "C5") (pin "1") (pinfunction "1_1") (pintype "passive"))
      (node (ref "C9") (pin "1") (pinfunction "1_1") (pintype "passive"))
      (node (ref "CN1S") (pin "7") (pinfunction "7_7") (pintype "passive"))
      (node (ref "CN1W") (pin "7") (pinfunction "7_7") (pintype "passive"))
      (node (ref "D1") (pin "2") (pinfunction "A_2") (pintype "passive"))
      (node (ref "D3") (pin "1") (pinfunction "K_1") (pintype "passive"))
      (node (ref "D4") (pin "1") (pinfunction "K_1") (pintype "passive"))
      (node (ref "M1") (pin "C17") (pinfunction "DETECT-IN_C17") (pintype "passive"))
      (node (ref "R1") (pin "1") (pinfunction "1_1") (pintype "passive"))
      (node (ref "R104") (pin "1") (pinfunction "1_1") (pintype "passive"))
      (node (ref "R4") (pin "2") (pinfunction "2_2") (pintype "passive"))
      (node (ref "R7") (pin "2") (pinfunction "2_2") (pintype "passive"))
      (node (ref "R8") (pin "2") (pinfunction "2_2") (pintype "passive"))
      (node (ref "R9") (pin "2") (pinfunction "2_2") (pintype "passive"))
      (node (ref "SW1A") (pin "1") (pinfunction "1_1") (pintype "passive"))
      (node (ref "TP76") (pin "1") (pinfunction "1_1") (pintype "passive"))
      (node (ref "U1") (pin "13") (pinfunction "VDDA_13") (pintype "power_in"))
      (node (ref "U1") (pin "18") (pinfunction "VSS_4_18") (pintype "power_in"))
      (node (ref "U1") (pin "32") (pinfunction "VDD_1_32") (pintype "power_in"))
      (node (ref "U1") (pin "48") (pinfunction "VDD_2_48") (pintype "power_in"))
      (node (ref "U1") (pin "64") (pinfunction "VDD_3_64") (pintype "power_in"))
      (node (ref "U2") (pin "8") (pinfunction "Vcc_8") (pintype "power_in"))
      (node (ref "U3") (pin "3") (pinfunction "E2_3") (pintype "passive"))
      (node (ref "U3") (pin "8") (pinfunction "Vcc_8") (pintype "power_in"))
    )
    (net (code "57") (name "3V3WIFI") (class "Default")
      (node (ref "C81") (pin "2") (pinfunction "2_2") (pintype "passive"))
      (node (ref "R106") (pin "2") (pinfunction "2_2") (pintype "passive"))
      (node (ref "U35") (pin "5") (pinfunction "Vout_5") (pintype "passive"))
    )
    (net (code "58") (name "4V") (class "Default")
      (node (ref "C16") (pin "2") (pinfunction "2_2") (pintype "passive"))
      (node (ref "D3") (pin "2") (pinfunction "A_2") (pintype "passive"))
      (node (ref "R11") (pin "2") (pinfunction "2_2") (pintype "passive"))
      (node (ref "TP71") (pin "1") (pinfunction "1_1") (pintype "passive"))
      (node (ref "U5") (pin "5") (pinfunction "VOUT_5") (pintype "passive"))
    )
    (net (code "59") (name "4VUSB") (class "Default")
      (node (ref "C18") (pin "2") (pinfunction "2_2") (pintype "passive"))
      (node (ref "D4") (pin "2") (pinfunction "A_2") (pintype "passive"))
      (node (ref "R16") (pin "2") (pinfunction "2_2") (pintype "passive"))
      (node (ref "TP70") (pin "1") (pinfunction "1_1") (pintype "passive"))
      (node (ref "U6") (pin "5") (pinfunction "VOUT_5") (pintype "passive"))
    )
    (net (code "60") (name "5V") (class "Default")
      (node (ref "C17") (pin "2") (pinfunction "2_2") (pintype "passive"))
      (node (ref "C79") (pin "1") (pinfunction "1_1") (pintype "passive"))
      (node (ref "C82") (pin "2") (pinfunction "2_2") (pintype "passive"))
      (node (ref "Q7") (pin "3") (pinfunction "D_3") (pintype "passive"))
      (node (ref "R100") (pin "2") (pinfunction "2_2") (pintype "passive"))
      (node (ref "R99") (pin "1") (pinfunction "1_1") (pintype "passive"))
      (node (ref "TP74") (pin "1") (pinfunction "1_1") (pintype "passive"))
      (node (ref "U35") (pin "1") (pinfunction "Vin_1") (pintype "passive"))
      (node (ref "U5") (pin "1") (pinfunction "VIN_1") (pintype "passive"))
    )
    (net (code "61") (name "5VUSB") (class "Default")
      (node (ref "C19") (pin "2") (pinfunction "2_2") (pintype "passive"))
      (node (ref "C20") (pin "1") (pinfunction "1_1") (pintype "passive"))
      (node (ref "C21") (pin "2") (pinfunction "2_2") (pintype "passive"))
      (node (ref "Q1") (pin "3") (pinfunction "D_3") (pintype "passive"))
      (node (ref "Q7") (pin "2") (pinfunction "S_2") (pintype "passive"))
      (node (ref "R19") (pin "1") (pinfunction "1_1") (pintype "passive"))
      (node (ref "R21") (pin "1") (pinfunction "1_1") (pintype "passive"))
      (node (ref "TP67") (pin "1") (pinfunction "1_1") (pintype "passive"))
      (node (ref "U6") (pin "1") (pinfunction "VIN_1") (pintype "passive"))
    )
    (net (code "62") (name "12V") (class "Default")
      (node (ref "R14") (pin "2") (pinfunction "2_2") (pintype "passive"))
    )
    (net (code "63") (name "GND") (class "Default")
      (node (ref "C1") (pin "2") (pinfunction "2_2") (pintype "passive"))
      (node (ref "C10") (pin "2") (pinfunction "2_2") (pintype "passive"))
      (node (ref "C11") (pin "2") (pinfunction "2_2") (pintype "passive"))
      (node (ref "C12") (pin "1") (pinfunction "1_1") (pintype "passive"))
      (node (ref "C13") (pin "1") (pinfunction "1_1") (pintype "passive"))
      (node (ref "C14") (pin "1") (pinfunction "1_1") (pintype "passive"))
      (node (ref "C16") (pin "1") (pinfunction "1_1") (pintype "passive"))
      (node (ref "C17") (pin "1") (pinfunction "1_1") (pintype "passive"))
      (node (ref "C18") (pin "1") (pinfunction "1_1") (pintype "passive"))
      (node (ref "C19") (pin "1") (pinfunction "1_1") (pintype "passive"))
      (node (ref "C2") (pin "2") (pinfunction "2_2") (pintype "passive"))
      (node (ref "C20") (pin "2") (pinfunction "2_2") (pintype "passive"))
      (node (ref "C22") (pin "2") (pinfunction "2_2") (pintype "passive"))
      (node (ref "C23") (pin "1") (pinfunction "1_1") (pintype "passive"))
      (node (ref "C24") (pin "2") (pinfunction "2_2") (pintype "passive"))
      (node (ref "C25") (pin "1") (pinfunction "1_1") (pintype "passive"))
      (node (ref "C26") (pin "1") (pinfunction "1_1") (pintype "passive"))
      (node (ref "C28") (pin "2") (pinfunction "2_2") (pintype "passive"))
      (node (ref "C3") (pin "2") (pinfunction "2_2") (pintype "passive"))
      (node (ref "C4") (pin "2") (pinfunction "2_2") (pintype "passive"))
      (node (ref "C5") (pin "2") (pinfunction "2_2") (pintype "passive"))
      (node (ref "C6") (pin "2") (pinfunction "2_2") (pintype "passive"))
      (node (ref "C7") (pin "1") (pinfunction "1_1") (pintype "passive"))
      (node (ref "C74") (pin "2") (pinfunction "2_2") (pintype "passive"))
      (node (ref "C75") (pin "2") (pinfunction "2_2") (pintype "passive"))
      (node (ref "C8") (pin "1") (pinfunction "1_1") (pintype "passive"))
      (node (ref "C81") (pin "1") (pinfunction "1_1") (pintype "passive"))
      (node (ref "C82") (pin "1") (pinfunction "1_1") (pintype "passive"))
      (node (ref "C9") (pin "2") (pinfunction "2_2") (pintype "passive"))
      (node (ref "CN1S") (pin "1") (pinfunction "1_1") (pintype "passive"))
      (node (ref "CN1W") (pin "1") (pinfunction "1_1") (pintype "passive"))
      (node (ref "L7") (pin "1") (pinfunction "1_1") (pintype "passive"))
      (node (ref "M1") (pin "A1") (pinfunction "GND_A1") (pintype "passive"))
      (node (ref "M1") (pin "A13") (pinfunction "GND_A13") (pintype "passive"))
      (node (ref "M1") (pin "A14") (pinfunction "GND_A14") (pintype "passive"))
      (node (ref "M1") (pin "A2") (pinfunction "GND_A2") (pintype "passive"))
      (node (ref "Q6") (pin "2") (pinfunction "S_2") (pintype "passive"))
      (node (ref "Q8") (pin "2") (pinfunction "E_2") (pintype "passive"))
      (node (ref "R102") (pin "2") (pinfunction "2_2") (pintype "passive"))
      (node (ref "R105") (pin "1") (pinfunction "1_1") (pintype "passive"))
      (node (ref "R13") (pin "1") (pinfunction "1_1") (pintype "passive"))
      (node (ref "R15") (pin "1") (pinfunction "1_1") (pintype "passive"))
      (node (ref "R18") (pin "1") (pinfunction "1_1") (pintype "passive"))
      (node (ref "R20") (pin "1") (pinfunction "1_1") (pintype "passive"))
      (node (ref "R27") (pin "1") (pinfunction "1_1") (pintype "passive"))
      (node (ref "R3") (pin "1") (pinfunction "1_1") (pintype "passive"))
      (node (ref "R5") (pin "1") (pinfunction "1_1") (pintype "passive"))
      (node (ref "R92") (pin "1") (pinfunction "1_1") (pintype "passive"))
      (node (ref "SW1B") (pin "2") (pinfunction "2_2") (pintype "passive"))
      (node (ref "TP180") (pin "1") (pinfunction "1_1") (pintype "passive"))
      (node (ref "U1") (pin "12") (pinfunction "VSSA_12") (pintype "power_in"))
      (node (ref "U1") (pin "19") (pinfunction "VDD_4_19") (pintype "power_in"))
      (node (ref "U1") (pin "31") (pinfunction "VSS_1_31") (pintype "power_in"))
      (node (ref "U1") (pin "47") (pinfunction "VSS_2_47") (pintype "power_in"))
      (node (ref "U1") (pin "63") (pinfunction "VSS_3_63") (pintype "power_in"))
      (node (ref "U2") (pin "3") (pinfunction "E2_3") (pintype "passive"))
      (node (ref "U2") (pin "4") (pinfunction "Vss_4") (pintype "power_in"))
      (node (ref "U3") (pin "4") (pinfunction "Vss_4") (pintype "power_in"))
      (node (ref "U35") (pin "2") (pinfunction "GND_2") (pintype "passive"))
      (node (ref "U5") (pin "2") (pinfunction "GND_2") (pintype "passive"))
      (node (ref "U6") (pin "2") (pinfunction "GND_2") (pintype "passive"))
      (node (ref "U7") (pin "13") (pinfunction "GND_13") (pintype "power_in"))
      (node (ref "U7") (pin "5") (pinfunction "GND_5") (pintype "power_in"))
      (node (ref "X1") (pin "2") (pinfunction "2_2") (pintype "passive"))
    )
    (net (code "64") (name "Net-(C27-Pad1)") (class "Default")
      (node (ref "C27") (pin "1") (pinfunction "1_1") (pintype "passive"))
      (node (ref "L1") (pin "2") (pinfunction "2_2") (pintype "passive"))
      (node (ref "P1") (pin "1") (pinfunction "1_1") (pintype "passive"))
      (node (ref "TP59") (pin "1") (pinfunction "1_1") (pintype "passive"))
    )
    (net (code "65") (name "Net-(CN2-D+)") (class "Default")
      (node (ref "C25") (pin "2") (pinfunction "2_2") (pintype "passive"))
      (node (ref "CN2") (pin "3") (pinfunction "D+_3") (pintype "passive"))
      (node (ref "R25") (pin "2") (pinfunction "2_2") (pintype "passive"))
      (node (ref "TP61") (pin "1") (pinfunction "1_1") (pintype "passive"))
      (node (ref "V1") (pin "2") (pinfunction "2_2") (pintype "passive"))
    )
    (net (code "66") (name "Net-(CN2-D-)") (class "Default")
      (node (ref "C26") (pin "2") (pinfunction "2_2") (pintype "passive"))
      (node (ref "CN2") (pin "2") (pinfunction "D-_2") (pintype "passive"))
      (node (ref "R24") (pin "2") (pinfunction "2_2") (pintype "passive"))
      (node (ref "TP62") (pin "1") (pinfunction "1_1") (pintype "passive"))
      (node (ref "V2") (pin "2") (pinfunction "2_2") (pintype "passive"))
    )
    (net (code "67") (name "Net-(CN2-GND)") (class "Default")
      (node (ref "C27") (pin "2") (pinfunction "2_2") (pintype "passive"))
      (node (ref "CN2") (pin "5") (pinfunction "GND_5") (pintype "passive"))
      (node (ref "L7") (pin "2") (pinfunction "2_2") (pintype "passive"))
      (node (ref "R92") (pin "2") (pinfunction "2_2") (pintype "passive"))
      (node (ref "TP75") (pin "1") (pinfunction "1_1") (pintype "passive"))
      (node (ref "V1") (pin "1") (pinfunction "1_1") (pintype "passive"))
      (node (ref "V2") (pin "1") (pinfunction "1_1") (pintype "passive"))
      (node (ref "V3") (pin "1") (pinfunction "1_1") (pintype "passive"))
    )
    (net (code "68") (name "Net-(CN2-VCC)") (class "Default")
      (node (ref "CN2") (pin "1") (pinfunction "VCC_1") (pintype "passive"))
      (node (ref "P1") (pin "2") (pinfunction "2_2") (pintype "passive"))
      (node (ref "TP58") (pin "1") (pinfunction "1_1") (pintype "passive"))
      (node (ref "V3") (pin "2") (pinfunction "2_2") (pintype "passive"))
    )
    (net (code "69") (name "Net-(D1-K)") (class "Default")
      (node (ref "C11") (pin "1") (pinfunction "1_1") (pintype "passive"))
      (node (ref "D1") (pin "1") (pinfunction "K_1") (pintype "passive"))
      (node (ref "R2") (pin "2") (pinfunction "2_2") (pintype "passive"))
      (node (ref "TP45") (pin "1") (pinfunction "1_1") (pintype "passive"))
    )
    (net (code "70") (name "Net-(M1-3V3-PadC14)") (class "Default")
      (node (ref "M1") (pin "C14") (pinfunction "3V3_C14") (pintype "passive"))
      (node (ref "M1") (pin "C15") (pinfunction "3V3_C15") (pintype "passive"))
      (node (ref "M1") (pin "C16") (pinfunction "3V3_C16") (pintype "passive"))
      (node (ref "R104") (pin "2") (pinfunction "2_2") (pintype "passive"))
      (node (ref "R106") (pin "1") (pinfunction "1_1") (pintype "passive"))
      (node (ref "TP190") (pin "1") (pinfunction "1_1") (pintype "passive"))
    )
    (net (code "71") (name "Net-(M1-CC_IO14_SCLK)") (class "Default")
      (node (ref "M1") (pin "A5") (pinfunction "CC_IO14_SCLK_A5") (pintype "passive"))
      (node (ref "R83") (pin "1") (pinfunction "1_1") (pintype "passive"))
      (node (ref "TP102") (pin "1") (pinfunction "1_1") (pintype "passive"))
    )
    (net (code "72") (name "Net-(M1-CC_IO15_SMISO)") (class "Default")
      (node (ref "M1") (pin "A6") (pinfunction "CC_IO15_SMISO_A6") (pintype "passive"))
      (node (ref "R82") (pin "1") (pinfunction "1_1") (pintype "passive"))
      (node (ref "TP103") (pin "1") (pinfunction "1_1") (pintype "passive"))
    )
    (net (code "73") (name "Net-(M1-CC_IO16_UTX_SMOSI)") (class "Default")
      (node (ref "M1") (pin "A7") (pinfunction "CC_IO16_UTX_SMOSI_A7") (pintype "passive"))
      (node (ref "R80") (pin "1") (pinfunction "1_1") (pintype "passive"))
      (node (ref "R81") (pin "1") (pinfunction "1_1") (pintype "passive"))
      (node (ref "TP104") (pin "1") (pinfunction "1_1") (pintype "passive"))
    )
    (net (code "74") (name "Net-(M1-CC_IO17_URX_SCS)") (class "Default")
      (node (ref "M1") (pin "A8") (pinfunction "CC_IO17_URX_SCS_A8") (pintype "passive"))
      (node (ref "R78") (pin "1") (pinfunction "1_1") (pintype "passive"))
      (node (ref "R79") (pin "1") (pinfunction "1_1") (pintype "passive"))
      (node (ref "TP105") (pin "1") (pinfunction "1_1") (pintype "passive"))
    )
    (net (code "75") (name "Net-(Q1-G)") (class "Default")
      (node (ref "C21") (pin "1") (pinfunction "1_1") (pintype "passive"))
      (node (ref "Q1") (pin "1") (pinfunction "G_1") (pintype "passive"))
      (node (ref "R22") (pin "2") (pinfunction "2_2") (pintype "passive"))
      (node (ref "R23") (pin "2") (pinfunction "2_2") (pintype "passive"))
      (node (ref "TP66") (pin "1") (pinfunction "1_1") (pintype "passive"))
    )
    (net (code "76") (name "Net-(Q1-S)") (class "Default")
      (node (ref "C22") (pin "1") (pinfunction "1_1") (pintype "passive"))
      (node (ref "C28") (pin "1") (pinfunction "1_1") (pintype "passive"))
      (node (ref "L1") (pin "1") (pinfunction "1_1") (pintype "passive"))
      (node (ref "Q1") (pin "2") (pinfunction "S_2") (pintype "passive"))
      (node (ref "R22") (pin "1") (pinfunction "1_1") (pintype "passive"))
      (node (ref "R26") (pin "2") (pinfunction "2_2") (pintype "passive"))
      (node (ref "TP60") (pin "1") (pinfunction "1_1") (pintype "passive"))
      (node (ref "U7") (pin "12") (pinfunction "VCC_12") (pintype "power_in"))
    )
    (net (code "77") (name "Net-(Q6-D)") (class "Default")
      (node (ref "C79") (pin "2") (pinfunction "2_2") (pintype "passive"))
      (node (ref "Q6") (pin "3") (pinfunction "D_3") (pintype "passive"))
      (node (ref "Q7") (pin "1") (pinfunction "G_1") (pintype "passive"))
      (node (ref "R21") (pin "2") (pinfunction "2_2") (pintype "passive"))
      (node (ref "TP181") (pin "1") (pinfunction "1_1") (pintype "passive"))
    )
    (net (code "78") (name "Net-(Q8-B)") (class "Default")
      (node (ref "Q8") (pin "1") (pinfunction "B_1") (pintype "passive"))
      (node (ref "R101") (pin "2") (pinfunction "2_2") (pintype "passive"))
    )
    (net (code "79") (name "Net-(Q8-C)") (class "Default")
      (node (ref "Q8") (pin "3") (pinfunction "C_3") (pintype "passive"))
      (node (ref "R100") (pin "1") (pinfunction "1_1") (pintype "passive"))
      (node (ref "TP188") (pin "1") (pinfunction "1_1") (pintype "passive"))
      (node (ref "U35") (pin "3") (pinfunction "EN_3") (pintype "passive"))
    )
    (net (code "80") (name "Net-(R11-Pad1)") (class "Default")
      (node (ref "R11") (pin "1") (pinfunction "1_1") (pintype "passive"))
      (node (ref "R12") (pin "2") (pinfunction "2_2") (pintype "passive"))
      (node (ref "TP73") (pin "1") (pinfunction "1_1") (pintype "passive"))
    )
    (net (code "81") (name "Net-(R16-Pad1)") (class "Default")
      (node (ref "R16") (pin "1") (pinfunction "1_1") (pintype "passive"))
      (node (ref "R17") (pin "2") (pinfunction "2_2") (pintype "passive"))
      (node (ref "TP69") (pin "1") (pinfunction "1_1") (pintype "passive"))
    )
    (net (code "82") (name "Net-(U1-PC8)") (class "Default")
      (node (ref "R103") (pin "2") (pinfunction "2_2") (pintype "passive"))
      (node (ref "TP87") (pin "1") (pinfunction "1_1") (pintype "passive"))
      (node (ref "U1") (pin "39") (pinfunction "PC8_39") (pintype "bidirectional"))
    )
    (net (code "83") (name "Net-(U1-PC14-OSC32_IN)") (class "Default")
      (node (ref "C6") (pin "1") (pinfunction "1_1") (pintype "passive"))
      (node (ref "U1") (pin "3") (pinfunction "PC14-OSC32_IN_3") (pintype "bidirectional"))
      (node (ref "X3") (pin "1") (pinfunction "1_1") (pintype "passive"))
    )
    (net (code "84") (name "Net-(U1-PC15-OSC32_OUT)") (class "Default")
      (node (ref "C7") (pin "2") (pinfunction "2_2") (pintype "passive"))
      (node (ref "U1") (pin "4") (pinfunction "PC15-OSC32_OUT_4") (pintype "bidirectional"))
      (node (ref "X3") (pin "4") (pinfunction "4_4") (pintype "passive"))
    )
    (net (code "85") (name "Net-(U1-PD0-OSC_IN)") (class "Default")
      (node (ref "U1") (pin "5") (pinfunction "PD0-OSC_IN_5") (pintype "bidirectional"))
      (node (ref "X1") (pin "1") (pinfunction "1_1") (pintype "passive"))
    )
    (net (code "86") (name "Net-(U1-PD1-OSC_OUT)") (class "Default")
      (node (ref "U1") (pin "6") (pinfunction "PD1-OSC_OUT_6") (pintype "bidirectional"))
      (node (ref "X1") (pin "3") (pinfunction "3_3") (pintype "passive"))
    )
    (net (code "87") (name "Net-(U1-VBAT)") (class "Default")
      (node (ref "R1") (pin "2") (pinfunction "2_2") (pintype "passive"))
      (node (ref "R2") (pin "1") (pinfunction "1_1") (pintype "passive"))
      (node (ref "TP47") (pin "1") (pinfunction "1_1") (pintype "passive"))
      (node (ref "U1") (pin "1") (pinfunction "VBAT_1") (pintype "power_in"))
    )
    (net (code "88") (name "Net-(U5-ADJ)") (class "Default")
      (node (ref "C74") (pin "1") (pinfunction "1_1") (pintype "passive"))
      (node (ref "R12") (pin "1") (pinfunction "1_1") (pintype "passive"))
      (node (ref "R13") (pin "2") (pinfunction "2_2") (pintype "passive"))
      (node (ref "TP72") (pin "1") (pinfunction "1_1") (pintype "passive"))
      (node (ref "U5") (pin "4") (pinfunction "ADJ_4") (pintype "passive"))
    )
    (net (code "89") (name "Net-(U5-EN)") (class "Default")
      (node (ref "R99") (pin "2") (pinfunction "2_2") (pintype "passive"))
      (node (ref "TP183") (pin "1") (pinfunction "1_1") (pintype "passive"))
      (node (ref "U5") (pin "3") (pinfunction "EN_3") (pintype "passive"))
    )
    (net (code "90") (name "Net-(U6-ADJ)") (class "Default")
      (node (ref "C75") (pin "1") (pinfunction "1_1") (pintype "passive"))
      (node (ref "R17") (pin "1") (pinfunction "1_1") (pintype "passive"))
      (node (ref "R18") (pin "2") (pinfunction "2_2") (pintype "passive"))
      (node (ref "TP68") (pin "1") (pinfunction "1_1") (pintype "passive"))
      (node (ref "U6") (pin "4") (pinfunction "ADJ_4") (pintype "passive"))
    )
    (net (code "91") (name "Net-(U6-EN)") (class "Default")
      (node (ref "R19") (pin "2") (pinfunction "2_2") (pintype "passive"))
      (node (ref "TP182") (pin "1") (pinfunction "1_1") (pintype "passive"))
      (node (ref "U6") (pin "3") (pinfunction "EN_3") (pintype "passive"))
    )
    (net (code "92") (name "Net-(U7-3V3OUT)") (class "Default")
      (node (ref "C23") (pin "2") (pinfunction "2_2") (pintype "passive"))
      (node (ref "R88") (pin "1") (pinfunction "1_1") (pintype "passive"))
      (node (ref "TP56") (pin "1") (pinfunction "1_1") (pintype "passive"))
      (node (ref "U7") (pin "10") (pinfunction "3V3OUT_10") (pintype "power_in"))
      (node (ref "U7") (pin "3") (pinfunction "VCCIO_3") (pintype "power_in"))
    )
    (net (code "93") (name "Net-(U7-RESET#)") (class "Default")
      (node (ref "C24") (pin "1") (pinfunction "1_1") (pintype "passive"))
      (node (ref "R26") (pin "1") (pinfunction "1_1") (pintype "passive"))
      (node (ref "R27") (pin "2") (pinfunction "2_2") (pintype "passive"))
      (node (ref "R88") (pin "2") (pinfunction "2_2") (pintype "passive"))
      (node (ref "TP57") (pin "1") (pinfunction "1_1") (pintype "passive"))
      (node (ref "U7") (pin "11") (pinfunction "RESET#_11") (pintype "passive"))
    )
    (net (code "94") (name "Net-(U7-USBDM)") (class "Default")
      (node (ref "R24") (pin "1") (pinfunction "1_1") (pintype "passive"))
      (node (ref "TP64") (pin "1") (pinfunction "1_1") (pintype "passive"))
      (node (ref "U7") (pin "9") (pinfunction "USBDM_9") (pintype "passive"))
    )
    (net (code "95") (name "Net-(U7-USBDP)") (class "Default")
      (node (ref "R25") (pin "1") (pinfunction "1_1") (pintype "passive"))
      (node (ref "TP63") (pin "1") (pinfunction "1_1") (pintype "passive"))
      (node (ref "U7") (pin "8") (pinfunction "USBDP_8") (pintype "passive"))
    )
    (net (code "96") (name "unconnected-(CN2-ID-Pad4)") (class "Default")
      (node (ref "CN2") (pin "4") (pinfunction "ID_4") (pintype "passive"))
    )
    (net (code "97") (name "unconnected-(U1-PB5-Pad57)") (class "Default")
      (node (ref "U1") (pin "57") (pinfunction "PB5_57") (pintype "bidirectional"))
    )
    (net (code "98") (name "unconnected-(U2-DU-Pad1)") (class "Default")
      (node (ref "U2") (pin "1") (pinfunction "DU_1") (pintype "passive"))
    )
    (net (code "99") (name "unconnected-(U2-DU-Pad2)") (class "Default")
      (node (ref "U2") (pin "2") (pinfunction "DU_2") (pintype "passive"))
    )
    (net (code "100") (name "unconnected-(U3-DU-Pad1)") (class "Default")
      (node (ref "U3") (pin "1") (pinfunction "DU_1") (pintype "passive"))
    )
    (net (code "101") (name "unconnected-(U3-DU-Pad2)") (class "Default")
      (node (ref "U3") (pin "2") (pinfunction "DU_2") (pintype "passive"))
    )
    (net (code "102") (name "unconnected-(U7-CBUS0-Pad15)") (class "Default")
      (node (ref "U7") (pin "15") (pinfunction "CBUS0_15") (pintype "passive"))
    )
    (net (code "103") (name "unconnected-(U7-CBUS1-Pad14)") (class "Default")
      (node (ref "U7") (pin "14") (pinfunction "CBUS1_14") (pintype "passive"))
    )
    (net (code "104") (name "unconnected-(U7-CBUS2-Pad7)") (class "Default")
      (node (ref "U7") (pin "7") (pinfunction "CBUS2_7") (pintype "passive"))
    )
    (net (code "105") (name "unconnected-(U7-CTS#-Pad6)") (class "Default")
      (node (ref "U7") (pin "6") (pinfunction "CTS#_6") (pintype "passive"))
    )
    (net (code "106") (name "unconnected-(U7-RTS#-Pad2)") (class "Default")
      (node (ref "U7") (pin "2") (pinfunction "RTS#_2") (pintype "passive"))
    )
    (net (code "107") (name "unconnected-(X3-Pad2)") (class "Default")
      (node (ref "X3") (pin "2") (pinfunction "2_2") (pintype "passive"))
    )
    (net (code "108") (name "unconnected-(X3-Pad3)") (class "Default")
      (node (ref "X3") (pin "3") (pinfunction "3_3") (pintype "passive"))
    )
  )
)
